# MBot.net
KiCad netlist of a schematic drawn in EAGLE
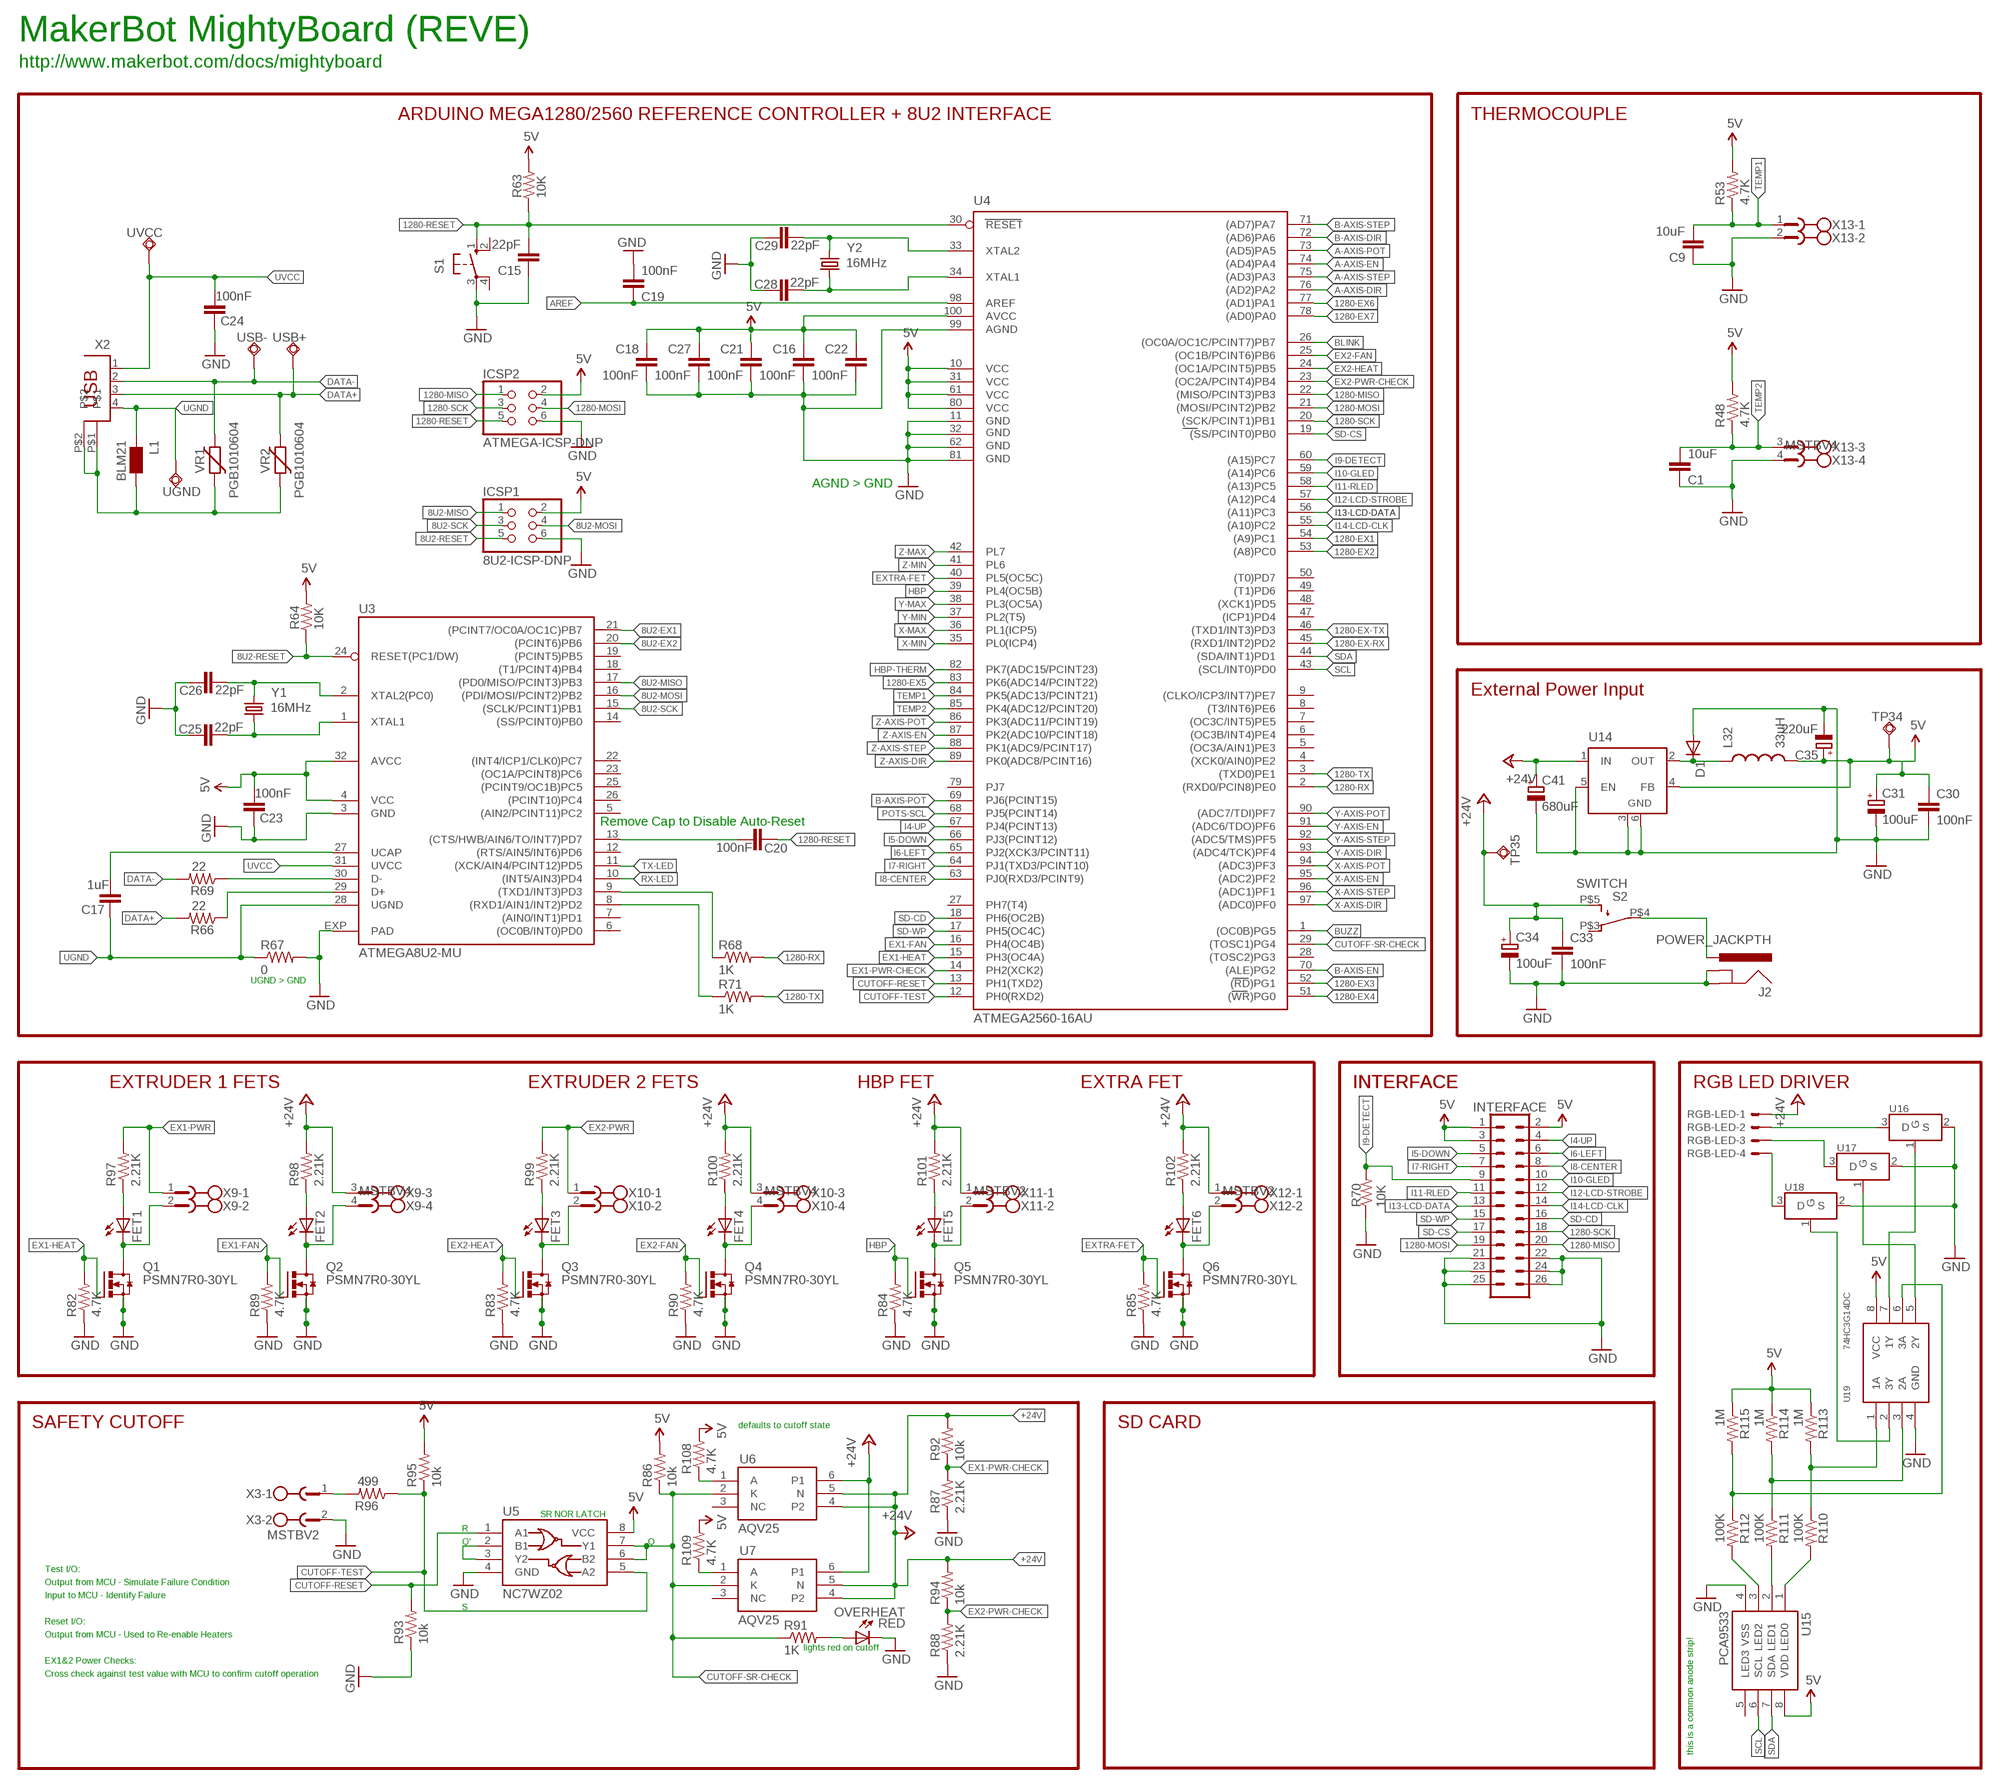
[diagram p0: schematic, sheet 1, part 1 of 2]
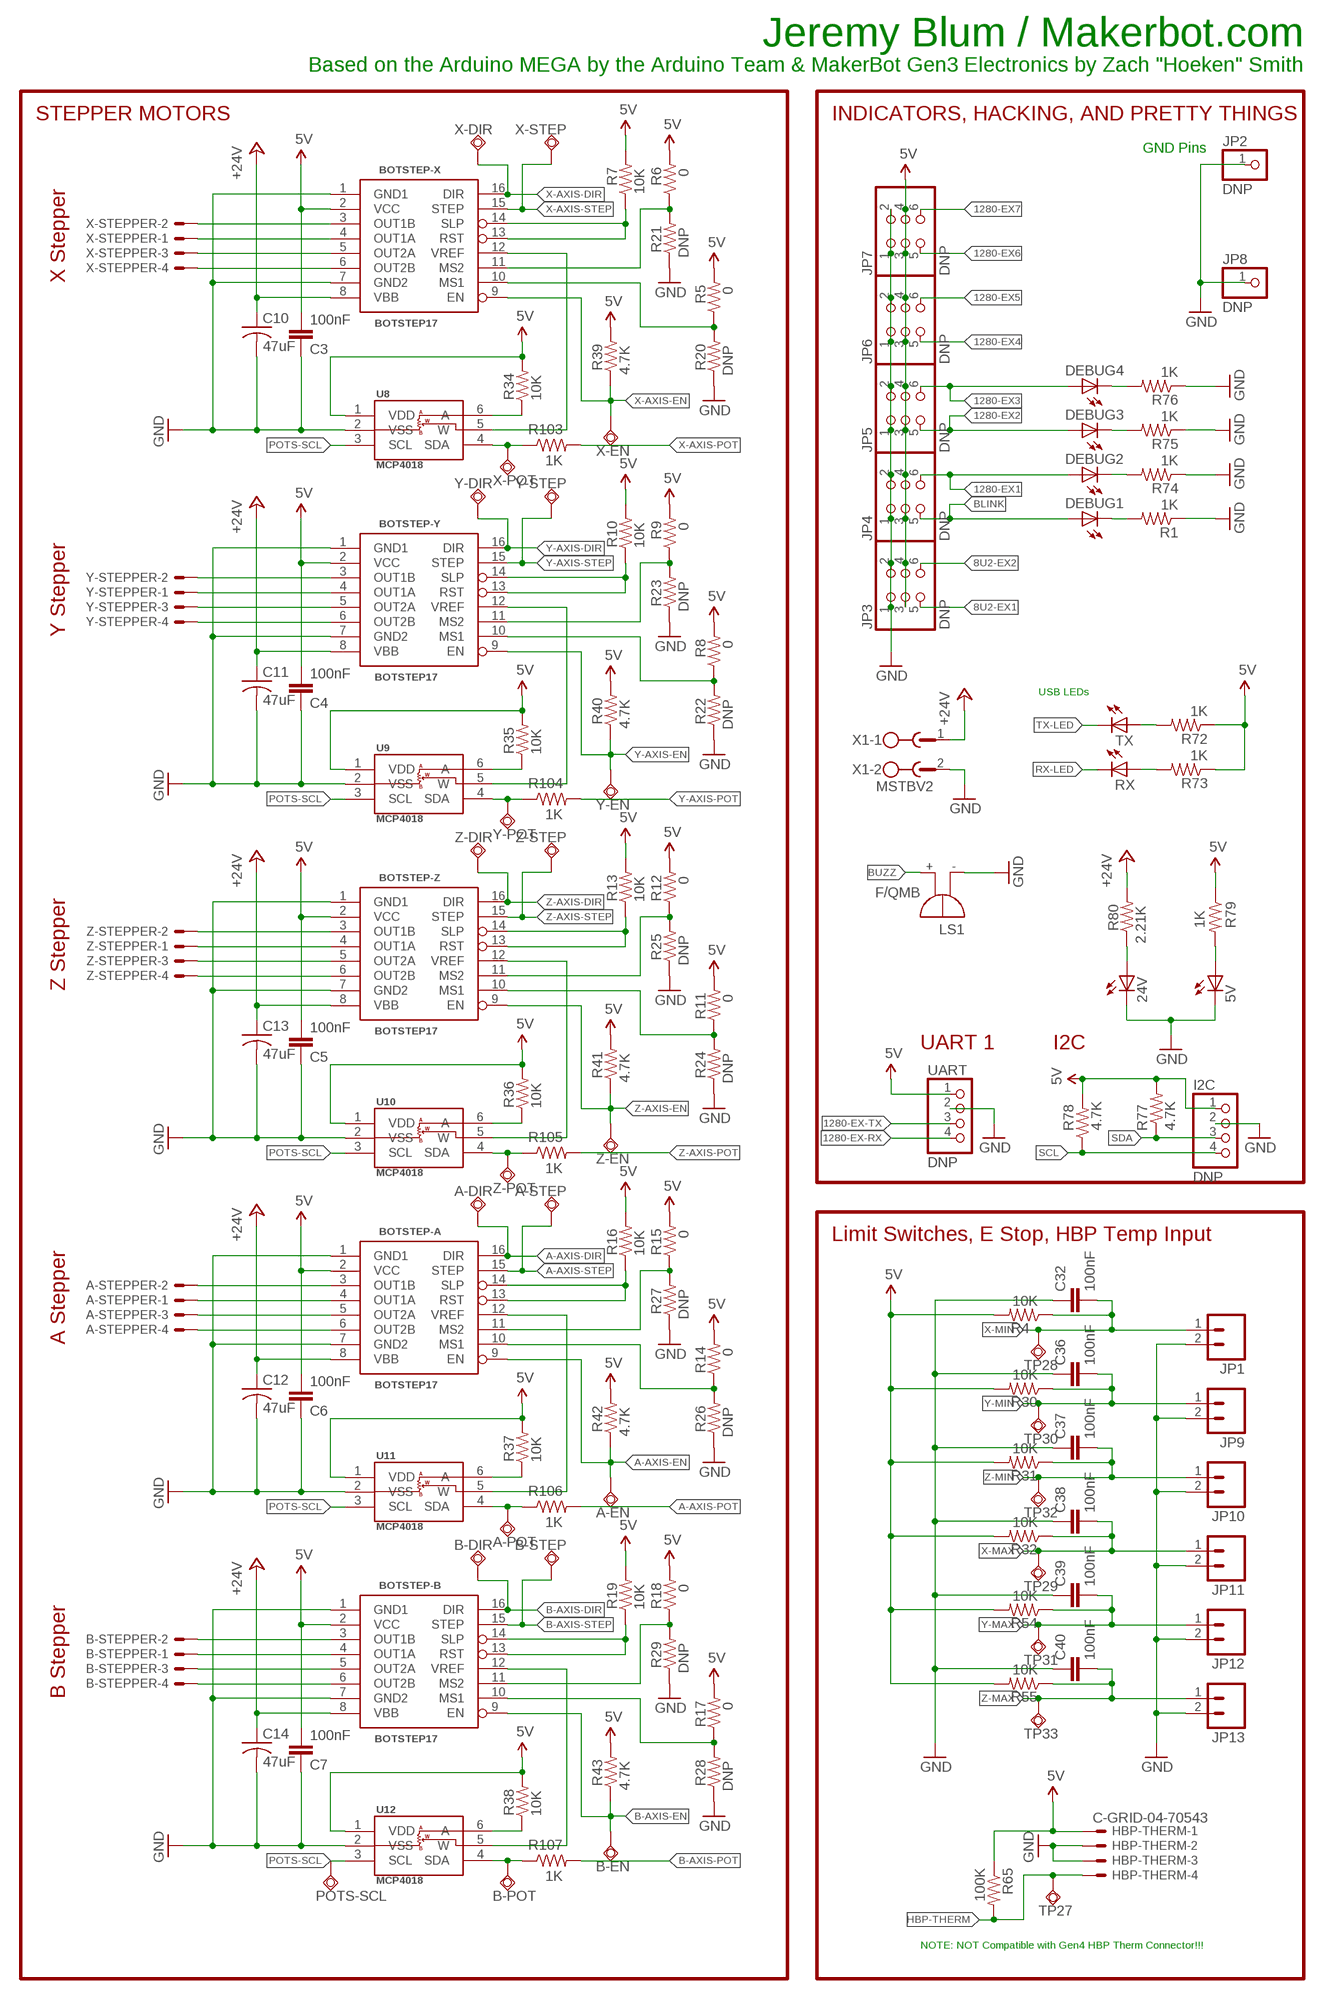
[diagram p1: schematic, sheet 1, part 2 of 2]

(export (version "E")
  (design (tool "Eeschema 10.0.6"))
  (components
    (comp (ref "5V")
      (value "GREEN")
      (footprint "eagle-import:LED-0805")
      (libsource (lib "eagle-import") (part "LED0805"))
    )
    (comp (ref "24V")
      (value "GREEN")
      (footprint "eagle-import:LED-0805")
      (libsource (lib "eagle-import") (part "LED0805"))
    )
    (comp (ref "A-DIR")
      (value "TPSQTP09R")
      (footprint "eagle-import:TP09R")
      (libsource (lib "eagle-import") (part "TPSQTP09R"))
    )
    (comp (ref "A-EN")
      (value "TPSQTP09R")
      (footprint "eagle-import:TP09R")
      (libsource (lib "eagle-import") (part "TPSQTP09R"))
    )
    (comp (ref "A-POT")
      (value "TPSQTP09R")
      (footprint "eagle-import:TP09R")
      (libsource (lib "eagle-import") (part "TPSQTP09R"))
    )
    (comp (ref "A-STEP")
      (value "TPSQTP09R")
      (footprint "eagle-import:TP09R")
      (libsource (lib "eagle-import") (part "TPSQTP09R"))
    )
    (comp (ref "A-STEPPER")
      (value "KK-156-4")
      (footprint "eagle-import:KK-156-4")
      (libsource (lib "eagle-import") (part "KK-156-4"))
    )
    (comp (ref "B-DIR")
      (value "TPSQTP09R")
      (footprint "eagle-import:TP09R")
      (libsource (lib "eagle-import") (part "TPSQTP09R"))
    )
    (comp (ref "B-EN")
      (value "TPSQTP09R")
      (footprint "eagle-import:TP09R")
      (libsource (lib "eagle-import") (part "TPSQTP09R"))
    )
    (comp (ref "B-POT")
      (value "TPSQTP09R")
      (footprint "eagle-import:TP09R")
      (libsource (lib "eagle-import") (part "TPSQTP09R"))
    )
    (comp (ref "B-STEP")
      (value "TPSQTP09R")
      (footprint "eagle-import:TP09R")
      (libsource (lib "eagle-import") (part "TPSQTP09R"))
    )
    (comp (ref "B-STEPPER")
      (value "KK-156-4")
      (footprint "eagle-import:KK-156-4")
      (libsource (lib "eagle-import") (part "KK-156-4"))
    )
    (comp (ref "BOTSTEP-A")
      (value "BOTSTEP17")
      (footprint "eagle-import:BOTSTEP17-INV")
      (libsource (lib "eagle-import") (part "BOTSTEP17CHIP-DOWN"))
    )
    (comp (ref "BOTSTEP-B")
      (value "BOTSTEP17")
      (footprint "eagle-import:BOTSTEP17-INV")
      (libsource (lib "eagle-import") (part "BOTSTEP17CHIP-DOWN"))
    )
    (comp (ref "BOTSTEP-X")
      (value "BOTSTEP17")
      (footprint "eagle-import:BOTSTEP17-INV")
      (libsource (lib "eagle-import") (part "BOTSTEP17CHIP-DOWN"))
    )
    (comp (ref "BOTSTEP-Y")
      (value "BOTSTEP17")
      (footprint "eagle-import:BOTSTEP17-INV")
      (libsource (lib "eagle-import") (part "BOTSTEP17CHIP-DOWN"))
    )
    (comp (ref "BOTSTEP-Z")
      (value "BOTSTEP17")
      (footprint "eagle-import:BOTSTEP17-INV")
      (libsource (lib "eagle-import") (part "BOTSTEP17CHIP-DOWN"))
    )
    (comp (ref "C1")
      (value "10uF")
      (footprint "eagle-import:0805")
      (libsource (lib "eagle-import") (part "CAP0805"))
    )
    (comp (ref "C3")
      (value "100nF")
      (footprint "eagle-import:0805")
      (libsource (lib "eagle-import") (part "CAP0805"))
    )
    (comp (ref "C4")
      (value "100nF")
      (footprint "eagle-import:0805")
      (libsource (lib "eagle-import") (part "CAP0805"))
    )
    (comp (ref "C5")
      (value "100nF")
      (footprint "eagle-import:0805")
      (libsource (lib "eagle-import") (part "CAP0805"))
    )
    (comp (ref "C6")
      (value "100nF")
      (footprint "eagle-import:0805")
      (libsource (lib "eagle-import") (part "CAP0805"))
    )
    (comp (ref "C7")
      (value "100nF")
      (footprint "eagle-import:0805")
      (libsource (lib "eagle-import") (part "CAP0805"))
    )
    (comp (ref "C9")
      (value "10uF")
      (footprint "eagle-import:0805")
      (libsource (lib "eagle-import") (part "CAP0805"))
    )
    (comp (ref "C10")
      (value "47uF")
      (footprint "eagle-import:CAP2917")
      (libsource (lib "eagle-import") (part "C-US"))
    )
    (comp (ref "C11")
      (value "47uF")
      (footprint "eagle-import:CAP2917")
      (libsource (lib "eagle-import") (part "C-US"))
    )
    (comp (ref "C12")
      (value "47uF")
      (footprint "eagle-import:CAP2917")
      (libsource (lib "eagle-import") (part "C-US"))
    )
    (comp (ref "C13")
      (value "47uF")
      (footprint "eagle-import:CAP2917")
      (libsource (lib "eagle-import") (part "C-US"))
    )
    (comp (ref "C14")
      (value "47uF")
      (footprint "eagle-import:CAP2917")
      (libsource (lib "eagle-import") (part "C-US"))
    )
    (comp (ref "C15")
      (value "22pF")
      (footprint "eagle-import:0805")
      (libsource (lib "eagle-import") (part "CAP0805"))
    )
    (comp (ref "C16")
      (value "100nF")
      (footprint "eagle-import:0805")
      (libsource (lib "eagle-import") (part "CAP0805"))
    )
    (comp (ref "C17")
      (value "1uF")
      (footprint "eagle-import:0805")
      (libsource (lib "eagle-import") (part "CAP0805"))
    )
    (comp (ref "C18")
      (value "100nF")
      (footprint "eagle-import:0805")
      (libsource (lib "eagle-import") (part "CAP0805"))
    )
    (comp (ref "C19")
      (value "100nF")
      (footprint "eagle-import:0805")
      (libsource (lib "eagle-import") (part "CAP0805"))
    )
    (comp (ref "C20")
      (value "100nF")
      (footprint "eagle-import:0805")
      (libsource (lib "eagle-import") (part "CAP0805"))
    )
    (comp (ref "C21")
      (value "100nF")
      (footprint "eagle-import:0805")
      (libsource (lib "eagle-import") (part "CAP0805"))
    )
    (comp (ref "C22")
      (value "100nF")
      (footprint "eagle-import:0805")
      (libsource (lib "eagle-import") (part "CAP0805"))
    )
    (comp (ref "C23")
      (value "100nF")
      (footprint "eagle-import:0805")
      (libsource (lib "eagle-import") (part "CAP0805"))
    )
    (comp (ref "C24")
      (value "100nF")
      (footprint "eagle-import:0805")
      (libsource (lib "eagle-import") (part "CAP0805"))
    )
    (comp (ref "C25")
      (value "22pF")
      (footprint "eagle-import:0805")
      (libsource (lib "eagle-import") (part "CAP0805"))
    )
    (comp (ref "C26")
      (value "22pF")
      (footprint "eagle-import:0805")
      (libsource (lib "eagle-import") (part "CAP0805"))
    )
    (comp (ref "C27")
      (value "100nF")
      (footprint "eagle-import:0805")
      (libsource (lib "eagle-import") (part "CAP0805"))
    )
    (comp (ref "C28")
      (value "22pF")
      (footprint "eagle-import:0805")
      (libsource (lib "eagle-import") (part "CAP0805"))
    )
    (comp (ref "C29")
      (value "22pF")
      (footprint "eagle-import:0805")
      (libsource (lib "eagle-import") (part "CAP0805"))
    )
    (comp (ref "C30")
      (value "100nF")
      (footprint "eagle-import:0805")
      (libsource (lib "eagle-import") (part "CAP0805"))
    )
    (comp (ref "C31")
      (value "100uF")
      (footprint "eagle-import:E3,5-8")
      (libsource (lib "eagle-import") (part "CPOL-EUE3.5-8"))
    )
    (comp (ref "C32")
      (value "100nF")
      (footprint "eagle-import:0805")
      (libsource (lib "eagle-import") (part "CAP0805"))
    )
    (comp (ref "C33")
      (value "100nF")
      (footprint "eagle-import:0805")
      (libsource (lib "eagle-import") (part "CAP0805"))
    )
    (comp (ref "C34")
      (value "100uF")
      (footprint "eagle-import:E3,5-8")
      (libsource (lib "eagle-import") (part "CPOL-EUE3.5-8"))
    )
    (comp (ref "C35")
      (value "220uF")
      (footprint "eagle-import:E3,5-8")
      (libsource (lib "eagle-import") (part "CPOL-EUE3.5-8"))
    )
    (comp (ref "C36")
      (value "100nF")
      (footprint "eagle-import:0805")
      (libsource (lib "eagle-import") (part "CAP0805"))
    )
    (comp (ref "C37")
      (value "100nF")
      (footprint "eagle-import:0805")
      (libsource (lib "eagle-import") (part "CAP0805"))
    )
    (comp (ref "C38")
      (value "100nF")
      (footprint "eagle-import:0805")
      (libsource (lib "eagle-import") (part "CAP0805"))
    )
    (comp (ref "C39")
      (value "100nF")
      (footprint "eagle-import:0805")
      (libsource (lib "eagle-import") (part "CAP0805"))
    )
    (comp (ref "C40")
      (value "100nF")
      (footprint "eagle-import:0805")
      (libsource (lib "eagle-import") (part "CAP0805"))
    )
    (comp (ref "C41")
      (value "680uF")
      (footprint "eagle-import:E3,5-8")
      (libsource (lib "eagle-import") (part "CPOL-EUE3.5-8"))
    )
    (comp (ref "D1")
      (value "DIODESMB")
      (footprint "eagle-import:SMB-DIODE")
      (libsource (lib "eagle-import") (part "DIODESMB"))
    )
    (comp (ref "DEBUG1")
      (value "GREEN")
      (footprint "eagle-import:LED-0805")
      (libsource (lib "eagle-import") (part "LED0805"))
    )
    (comp (ref "DEBUG2")
      (value "GREEN")
      (footprint "eagle-import:LED-0805")
      (libsource (lib "eagle-import") (part "LED0805"))
    )
    (comp (ref "DEBUG3")
      (value "GREEN")
      (footprint "eagle-import:LED-0805")
      (libsource (lib "eagle-import") (part "LED0805"))
    )
    (comp (ref "DEBUG4")
      (value "GREEN")
      (footprint "eagle-import:LED-0805")
      (libsource (lib "eagle-import") (part "LED0805"))
    )
    (comp (ref "FET1")
      (value "GREEN")
      (footprint "eagle-import:LED-0805")
      (libsource (lib "eagle-import") (part "LED0805"))
    )
    (comp (ref "FET2")
      (value "GREEN")
      (footprint "eagle-import:LED-0805")
      (libsource (lib "eagle-import") (part "LED0805"))
    )
    (comp (ref "FET3")
      (value "GREEN")
      (footprint "eagle-import:LED-0805")
      (libsource (lib "eagle-import") (part "LED0805"))
    )
    (comp (ref "FET4")
      (value "GREEN")
      (footprint "eagle-import:LED-0805")
      (libsource (lib "eagle-import") (part "LED0805"))
    )
    (comp (ref "FET5")
      (value "GREEN")
      (footprint "eagle-import:LED-0805")
      (libsource (lib "eagle-import") (part "LED0805"))
    )
    (comp (ref "FET6")
      (value "GREEN")
      (footprint "eagle-import:LED-0805")
      (libsource (lib "eagle-import") (part "LED0805"))
    )
    (comp (ref "HBP-THERM")
      (value "C-GRID-04-70543")
      (footprint "eagle-import:70543-04")
      (libsource (lib "eagle-import") (part "C-GRID-04-70543"))
    )
    (comp (ref "I2C")
      (value "DNP")
      (footprint "eagle-import:1X04")
      (libsource (lib "eagle-import") (part "PINHD-1X4"))
    )
    (comp (ref "ICSP1")
      (value "8U2-ICSP-DNP")
      (footprint "eagle-import:2X03")
      (libsource (lib "eagle-import") (part "PINHD-2X3"))
    )
    (comp (ref "ICSP2")
      (value "ATMEGA-ICSP-DNP")
      (footprint "eagle-import:2X03")
      (libsource (lib "eagle-import") (part "PINHD-2X3"))
    )
    (comp (ref "INTERFACE")
      (value "ML26")
      (footprint "eagle-import:ML26")
      (libsource (lib "eagle-import") (part "ML26"))
    )
    (comp (ref "J2")
      (value "POWER_JACKPTH")
      (footprint "eagle-import:POWER_JACK_PTH")
      (libsource (lib "eagle-import") (part "POWER_JACKPTH"))
    )
    (comp (ref "JP1")
      (value "M02POLAR")
      (footprint "eagle-import:MOLEX-1X2")
      (libsource (lib "eagle-import") (part "M02POLAR"))
    )
    (comp (ref "JP2")
      (value "DNP")
      (footprint "eagle-import:1X01")
      (libsource (lib "eagle-import") (part "PINHD-1X1"))
    )
    (comp (ref "JP3")
      (value "DNP")
      (footprint "eagle-import:2X03")
      (libsource (lib "eagle-import") (part "PINHD-2X3"))
    )
    (comp (ref "JP4")
      (value "DNP")
      (footprint "eagle-import:2X03")
      (libsource (lib "eagle-import") (part "PINHD-2X3"))
    )
    (comp (ref "JP5")
      (value "DNP")
      (footprint "eagle-import:2X03")
      (libsource (lib "eagle-import") (part "PINHD-2X3"))
    )
    (comp (ref "JP6")
      (value "DNP")
      (footprint "eagle-import:2X03")
      (libsource (lib "eagle-import") (part "PINHD-2X3"))
    )
    (comp (ref "JP7")
      (value "DNP")
      (footprint "eagle-import:2X03")
      (libsource (lib "eagle-import") (part "PINHD-2X3"))
    )
    (comp (ref "JP8")
      (value "DNP")
      (footprint "eagle-import:1X01")
      (libsource (lib "eagle-import") (part "PINHD-1X1"))
    )
    (comp (ref "JP9")
      (value "M02POLAR")
      (footprint "eagle-import:MOLEX-1X2")
      (libsource (lib "eagle-import") (part "M02POLAR"))
    )
    (comp (ref "JP10")
      (value "M02POLAR")
      (footprint "eagle-import:MOLEX-1X2")
      (libsource (lib "eagle-import") (part "M02POLAR"))
    )
    (comp (ref "JP11")
      (value "M02POLAR")
      (footprint "eagle-import:MOLEX-1X2")
      (libsource (lib "eagle-import") (part "M02POLAR"))
    )
    (comp (ref "JP12")
      (value "M02POLAR")
      (footprint "eagle-import:MOLEX-1X2")
      (libsource (lib "eagle-import") (part "M02POLAR"))
    )
    (comp (ref "JP13")
      (value "M02POLAR")
      (footprint "eagle-import:MOLEX-1X2")
      (libsource (lib "eagle-import") (part "M02POLAR"))
    )
    (comp (ref "L1")
      (value "BLM21")
      (footprint "eagle-import:0805")
      (libsource (lib "eagle-import") (part "WE-CBF_0805"))
    )
    (comp (ref "L32")
      (value "33uH")
      (footprint "eagle-import:CDRH125")
      (libsource (lib "eagle-import") (part "INDUCTORPWR"))
    )
    (comp (ref "LS1")
      (value "F/QMB")
      (footprint "eagle-import:F_QMB")
      (libsource (lib "eagle-import") (part "F/QMB"))
    )
    (comp (ref "OVERHEAT")
      (value "RED")
      (footprint "eagle-import:LED-0805")
      (libsource (lib "eagle-import") (part "LED0805"))
    )
    (comp (ref "POTS-SCL")
      (value "TPSQTP09R")
      (footprint "eagle-import:TP09R")
      (libsource (lib "eagle-import") (part "TPSQTP09R"))
    )
    (comp (ref "Q1")
      (value "PSMN7R0-30YL")
      (footprint "eagle-import:SOT669")
      (libsource (lib "eagle-import") (part "PSMN7R0-30YL"))
    )
    (comp (ref "Q2")
      (value "PSMN7R0-30YL")
      (footprint "eagle-import:SOT669")
      (libsource (lib "eagle-import") (part "PSMN7R0-30YL"))
    )
    (comp (ref "Q3")
      (value "PSMN7R0-30YL")
      (footprint "eagle-import:SOT669")
      (libsource (lib "eagle-import") (part "PSMN7R0-30YL"))
    )
    (comp (ref "Q4")
      (value "PSMN7R0-30YL")
      (footprint "eagle-import:SOT669")
      (libsource (lib "eagle-import") (part "PSMN7R0-30YL"))
    )
    (comp (ref "Q5")
      (value "PSMN7R0-30YL")
      (footprint "eagle-import:SOT669")
      (libsource (lib "eagle-import") (part "PSMN7R0-30YL"))
    )
    (comp (ref "Q6")
      (value "PSMN7R0-30YL")
      (footprint "eagle-import:SOT669")
      (libsource (lib "eagle-import") (part "PSMN7R0-30YL"))
    )
    (comp (ref "R1")
      (value "1K")
      (footprint "eagle-import:0805")
      (libsource (lib "eagle-import") (part "RESISTOR"))
    )
    (comp (ref "R4")
      (value "10K")
      (footprint "eagle-import:0805")
      (libsource (lib "eagle-import") (part "RESISTOR"))
    )
    (comp (ref "R5")
      (value "0")
      (footprint "eagle-import:0805")
      (libsource (lib "eagle-import") (part "RESISTOR"))
    )
    (comp (ref "R6")
      (value "0")
      (footprint "eagle-import:0805")
      (libsource (lib "eagle-import") (part "RESISTOR"))
    )
    (comp (ref "R7")
      (value "10K")
      (footprint "eagle-import:0805")
      (libsource (lib "eagle-import") (part "RESISTOR"))
    )
    (comp (ref "R8")
      (value "0")
      (footprint "eagle-import:0805")
      (libsource (lib "eagle-import") (part "RESISTOR"))
    )
    (comp (ref "R9")
      (value "0")
      (footprint "eagle-import:0805")
      (libsource (lib "eagle-import") (part "RESISTOR"))
    )
    (comp (ref "R10")
      (value "10K")
      (footprint "eagle-import:0805")
      (libsource (lib "eagle-import") (part "RESISTOR"))
    )
    (comp (ref "R11")
      (value "0")
      (footprint "eagle-import:0805")
      (libsource (lib "eagle-import") (part "RESISTOR"))
    )
    (comp (ref "R12")
      (value "0")
      (footprint "eagle-import:0805")
      (libsource (lib "eagle-import") (part "RESISTOR"))
    )
    (comp (ref "R13")
      (value "10K")
      (footprint "eagle-import:0805")
      (libsource (lib "eagle-import") (part "RESISTOR"))
    )
    (comp (ref "R14")
      (value "0")
      (footprint "eagle-import:0805")
      (libsource (lib "eagle-import") (part "RESISTOR"))
    )
    (comp (ref "R15")
      (value "0")
      (footprint "eagle-import:0805")
      (libsource (lib "eagle-import") (part "RESISTOR"))
    )
    (comp (ref "R16")
      (value "10K")
      (footprint "eagle-import:0805")
      (libsource (lib "eagle-import") (part "RESISTOR"))
    )
    (comp (ref "R17")
      (value "0")
      (footprint "eagle-import:0805")
      (libsource (lib "eagle-import") (part "RESISTOR"))
    )
    (comp (ref "R18")
      (value "0")
      (footprint "eagle-import:0805")
      (libsource (lib "eagle-import") (part "RESISTOR"))
    )
    (comp (ref "R19")
      (value "10K")
      (footprint "eagle-import:0805")
      (libsource (lib "eagle-import") (part "RESISTOR"))
    )
    (comp (ref "R20")
      (value "DNP")
      (footprint "eagle-import:0805")
      (libsource (lib "eagle-import") (part "RESISTOR"))
    )
    (comp (ref "R21")
      (value "DNP")
      (footprint "eagle-import:0805")
      (libsource (lib "eagle-import") (part "RESISTOR"))
    )
    (comp (ref "R22")
      (value "DNP")
      (footprint "eagle-import:0805")
      (libsource (lib "eagle-import") (part "RESISTOR"))
    )
    (comp (ref "R23")
      (value "DNP")
      (footprint "eagle-import:0805")
      (libsource (lib "eagle-import") (part "RESISTOR"))
    )
    (comp (ref "R24")
      (value "DNP")
      (footprint "eagle-import:0805")
      (libsource (lib "eagle-import") (part "RESISTOR"))
    )
    (comp (ref "R25")
      (value "DNP")
      (footprint "eagle-import:0805")
      (libsource (lib "eagle-import") (part "RESISTOR"))
    )
    (comp (ref "R26")
      (value "DNP")
      (footprint "eagle-import:0805")
      (libsource (lib "eagle-import") (part "RESISTOR"))
    )
    (comp (ref "R27")
      (value "DNP")
      (footprint "eagle-import:0805")
      (libsource (lib "eagle-import") (part "RESISTOR"))
    )
    (comp (ref "R28")
      (value "DNP")
      (footprint "eagle-import:0805")
      (libsource (lib "eagle-import") (part "RESISTOR"))
    )
    (comp (ref "R29")
      (value "DNP")
      (footprint "eagle-import:0805")
      (libsource (lib "eagle-import") (part "RESISTOR"))
    )
    (comp (ref "R30")
      (value "10K")
      (footprint "eagle-import:0805")
      (libsource (lib "eagle-import") (part "RESISTOR"))
    )
    (comp (ref "R31")
      (value "10K")
      (footprint "eagle-import:0805")
      (libsource (lib "eagle-import") (part "RESISTOR"))
    )
    (comp (ref "R32")
      (value "10K")
      (footprint "eagle-import:0805")
      (libsource (lib "eagle-import") (part "RESISTOR"))
    )
    (comp (ref "R34")
      (value "10K")
      (footprint "eagle-import:0805")
      (libsource (lib "eagle-import") (part "RESISTOR"))
    )
    (comp (ref "R35")
      (value "10K")
      (footprint "eagle-import:0805")
      (libsource (lib "eagle-import") (part "RESISTOR"))
    )
    (comp (ref "R36")
      (value "10K")
      (footprint "eagle-import:0805")
      (libsource (lib "eagle-import") (part "RESISTOR"))
    )
    (comp (ref "R37")
      (value "10K")
      (footprint "eagle-import:0805")
      (libsource (lib "eagle-import") (part "RESISTOR"))
    )
    (comp (ref "R38")
      (value "10K")
      (footprint "eagle-import:0805")
      (libsource (lib "eagle-import") (part "RESISTOR"))
    )
    (comp (ref "R39")
      (value "4.7K")
      (footprint "eagle-import:0805")
      (libsource (lib "eagle-import") (part "RESISTOR"))
    )
    (comp (ref "R40")
      (value "4.7K")
      (footprint "eagle-import:0805")
      (libsource (lib "eagle-import") (part "RESISTOR"))
    )
    (comp (ref "R41")
      (value "4.7K")
      (footprint "eagle-import:0805")
      (libsource (lib "eagle-import") (part "RESISTOR"))
    )
    (comp (ref "R42")
      (value "4.7K")
      (footprint "eagle-import:0805")
      (libsource (lib "eagle-import") (part "RESISTOR"))
    )
    (comp (ref "R43")
      (value "4.7K")
      (footprint "eagle-import:0805")
      (libsource (lib "eagle-import") (part "RESISTOR"))
    )
    (comp (ref "R48")
      (value "4.7K")
      (footprint "eagle-import:0805")
      (libsource (lib "eagle-import") (part "RESISTOR"))
    )
    (comp (ref "R53")
      (value "4.7K")
      (footprint "eagle-import:0805")
      (libsource (lib "eagle-import") (part "RESISTOR"))
    )
    (comp (ref "R54")
      (value "10K")
      (footprint "eagle-import:0805")
      (libsource (lib "eagle-import") (part "RESISTOR"))
    )
    (comp (ref "R55")
      (value "10K")
      (footprint "eagle-import:0805")
      (libsource (lib "eagle-import") (part "RESISTOR"))
    )
    (comp (ref "R63")
      (value "10K")
      (footprint "eagle-import:0805")
      (libsource (lib "eagle-import") (part "RESISTOR"))
    )
    (comp (ref "R64")
      (value "10K")
      (footprint "eagle-import:0805")
      (libsource (lib "eagle-import") (part "RESISTOR"))
    )
    (comp (ref "R65")
      (value "100K")
      (footprint "eagle-import:0805")
      (libsource (lib "eagle-import") (part "RESISTOR"))
    )
    (comp (ref "R66")
      (value "22")
      (footprint "eagle-import:0805")
      (libsource (lib "eagle-import") (part "RESISTOR"))
    )
    (comp (ref "R67")
      (value "0")
      (footprint "eagle-import:0805")
      (libsource (lib "eagle-import") (part "RESISTOR"))
    )
    (comp (ref "R68")
      (value "1K")
      (footprint "eagle-import:0805")
      (libsource (lib "eagle-import") (part "RESISTOR"))
    )
    (comp (ref "R69")
      (value "22")
      (footprint "eagle-import:0805")
      (libsource (lib "eagle-import") (part "RESISTOR"))
    )
    (comp (ref "R70")
      (value "10K")
      (footprint "eagle-import:0805")
      (libsource (lib "eagle-import") (part "RESISTOR"))
    )
    (comp (ref "R71")
      (value "1K")
      (footprint "eagle-import:0805")
      (libsource (lib "eagle-import") (part "RESISTOR"))
    )
    (comp (ref "R72")
      (value "1K")
      (footprint "eagle-import:0805")
      (libsource (lib "eagle-import") (part "RESISTOR"))
    )
    (comp (ref "R73")
      (value "1K")
      (footprint "eagle-import:0805")
      (libsource (lib "eagle-import") (part "RESISTOR"))
    )
    (comp (ref "R74")
      (value "1K")
      (footprint "eagle-import:0805")
      (libsource (lib "eagle-import") (part "RESISTOR"))
    )
    (comp (ref "R75")
      (value "1K")
      (footprint "eagle-import:0805")
      (libsource (lib "eagle-import") (part "RESISTOR"))
    )
    (comp (ref "R76")
      (value "1K")
      (footprint "eagle-import:0805")
      (libsource (lib "eagle-import") (part "RESISTOR"))
    )
    (comp (ref "R77")
      (value "4.7K")
      (footprint "eagle-import:0805")
      (libsource (lib "eagle-import") (part "RESISTOR"))
    )
    (comp (ref "R78")
      (value "4.7K")
      (footprint "eagle-import:0805")
      (libsource (lib "eagle-import") (part "RESISTOR"))
    )
    (comp (ref "R79")
      (value "1K")
      (footprint "eagle-import:0805")
      (libsource (lib "eagle-import") (part "RESISTOR"))
    )
    (comp (ref "R80")
      (value "2.21K")
      (footprint "eagle-import:0805")
      (libsource (lib "eagle-import") (part "RESISTOR"))
    )
    (comp (ref "R82")
      (value "4.7K")
      (footprint "eagle-import:0805")
      (libsource (lib "eagle-import") (part "RESISTOR"))
    )
    (comp (ref "R83")
      (value "4.7K")
      (footprint "eagle-import:0805")
      (libsource (lib "eagle-import") (part "RESISTOR"))
    )
    (comp (ref "R84")
      (value "4.7K")
      (footprint "eagle-import:0805")
      (libsource (lib "eagle-import") (part "RESISTOR"))
    )
    (comp (ref "R85")
      (value "4.7K")
      (footprint "eagle-import:0805")
      (libsource (lib "eagle-import") (part "RESISTOR"))
    )
    (comp (ref "R86")
      (value "10k")
      (footprint "eagle-import:0805")
      (libsource (lib "eagle-import") (part "RESISTOR"))
    )
    (comp (ref "R87")
      (value "2.21K")
      (footprint "eagle-import:0805")
      (libsource (lib "eagle-import") (part "RESISTOR"))
    )
    (comp (ref "R88")
      (value "2.21K")
      (footprint "eagle-import:0805")
      (libsource (lib "eagle-import") (part "RESISTOR"))
    )
    (comp (ref "R89")
      (value "4.7K")
      (footprint "eagle-import:0805")
      (libsource (lib "eagle-import") (part "RESISTOR"))
    )
    (comp (ref "R90")
      (value "4.7K")
      (footprint "eagle-import:0805")
      (libsource (lib "eagle-import") (part "RESISTOR"))
    )
    (comp (ref "R91")
      (value "1K")
      (footprint "eagle-import:0805")
      (libsource (lib "eagle-import") (part "RESISTOR"))
    )
    (comp (ref "R92")
      (value "10k")
      (footprint "eagle-import:0805")
      (libsource (lib "eagle-import") (part "RESISTOR"))
    )
    (comp (ref "R93")
      (value "10k")
      (footprint "eagle-import:0805")
      (libsource (lib "eagle-import") (part "RESISTOR"))
    )
    (comp (ref "R94")
      (value "10k")
      (footprint "eagle-import:0805")
      (libsource (lib "eagle-import") (part "RESISTOR"))
    )
    (comp (ref "R95")
      (value "10k")
      (footprint "eagle-import:0805")
      (libsource (lib "eagle-import") (part "RESISTOR"))
    )
    (comp (ref "R96")
      (value "499")
      (footprint "eagle-import:0805")
      (libsource (lib "eagle-import") (part "RESISTOR"))
    )
    (comp (ref "R97")
      (value "2.21K")
      (footprint "eagle-import:0805")
      (libsource (lib "eagle-import") (part "RESISTOR"))
    )
    (comp (ref "R98")
      (value "2.21K")
      (footprint "eagle-import:0805")
      (libsource (lib "eagle-import") (part "RESISTOR"))
    )
    (comp (ref "R99")
      (value "2.21K")
      (footprint "eagle-import:0805")
      (libsource (lib "eagle-import") (part "RESISTOR"))
    )
    (comp (ref "R100")
      (value "2.21K")
      (footprint "eagle-import:0805")
      (libsource (lib "eagle-import") (part "RESISTOR"))
    )
    (comp (ref "R101")
      (value "2.21K")
      (footprint "eagle-import:0805")
      (libsource (lib "eagle-import") (part "RESISTOR"))
    )
    (comp (ref "R102")
      (value "2.21K")
      (footprint "eagle-import:0805")
      (libsource (lib "eagle-import") (part "RESISTOR"))
    )
    (comp (ref "R103")
      (value "1K")
      (footprint "eagle-import:0805")
      (libsource (lib "eagle-import") (part "RESISTOR"))
    )
    (comp (ref "R104")
      (value "1K")
      (footprint "eagle-import:0805")
      (libsource (lib "eagle-import") (part "RESISTOR"))
    )
    (comp (ref "R105")
      (value "1K")
      (footprint "eagle-import:0805")
      (libsource (lib "eagle-import") (part "RESISTOR"))
    )
    (comp (ref "R106")
      (value "1K")
      (footprint "eagle-import:0805")
      (libsource (lib "eagle-import") (part "RESISTOR"))
    )
    (comp (ref "R107")
      (value "1K")
      (footprint "eagle-import:0805")
      (libsource (lib "eagle-import") (part "RESISTOR"))
    )
    (comp (ref "R108")
      (value "4.7K")
      (footprint "eagle-import:0805")
      (libsource (lib "eagle-import") (part "RESISTOR"))
    )
    (comp (ref "R109")
      (value "4.7K")
      (footprint "eagle-import:0805")
      (libsource (lib "eagle-import") (part "RESISTOR"))
    )
    (comp (ref "R110")
      (value "100K")
      (footprint "eagle-import:0805")
      (libsource (lib "eagle-import") (part "RESISTOR"))
    )
    (comp (ref "R111")
      (value "100K")
      (footprint "eagle-import:0805")
      (libsource (lib "eagle-import") (part "RESISTOR"))
    )
    (comp (ref "R112")
      (value "100K")
      (footprint "eagle-import:0805")
      (libsource (lib "eagle-import") (part "RESISTOR"))
    )
    (comp (ref "R113")
      (value "1M")
      (footprint "eagle-import:0805")
      (libsource (lib "eagle-import") (part "RESISTOR"))
    )
    (comp (ref "R114")
      (value "1M")
      (footprint "eagle-import:0805")
      (libsource (lib "eagle-import") (part "RESISTOR"))
    )
    (comp (ref "R115")
      (value "1M")
      (footprint "eagle-import:0805")
      (libsource (lib "eagle-import") (part "RESISTOR"))
    )
    (comp (ref "RGB-LED")
      (value "C-GRID-04-70543")
      (footprint "eagle-import:70543-04")
      (libsource (lib "eagle-import") (part "C-GRID-04-70543"))
    )
    (comp (ref "RX")
      (value "GREEN")
      (footprint "eagle-import:LED-0805")
      (libsource (lib "eagle-import") (part "LED0805"))
    )
    (comp (ref "S1")
      (value "10-XX")
      (footprint "eagle-import:B3F-10XX")
      (fields (field (name "MPN") "B3F-1000"))
      (libsource (lib "eagle-import") (part "10-XX"))
    )
    (comp (ref "S2")
      (value "SWITCH")
      (footprint "eagle-import:SWITCH")
      (libsource (lib "eagle-import") (part "SWITCH"))
    )
    (comp (ref "TP27")
      (value "TPSQTP09R")
      (footprint "eagle-import:TP09R")
      (libsource (lib "eagle-import") (part "TPSQTP09R"))
    )
    (comp (ref "TP28")
      (value "TPSQTP09R")
      (footprint "eagle-import:TP09R")
      (libsource (lib "eagle-import") (part "TPSQTP09R"))
    )
    (comp (ref "TP29")
      (value "TPSQTP09R")
      (footprint "eagle-import:TP09R")
      (libsource (lib "eagle-import") (part "TPSQTP09R"))
    )
    (comp (ref "TP30")
      (value "TPSQTP09R")
      (footprint "eagle-import:TP09R")
      (libsource (lib "eagle-import") (part "TPSQTP09R"))
    )
    (comp (ref "TP31")
      (value "TPSQTP09R")
      (footprint "eagle-import:TP09R")
      (libsource (lib "eagle-import") (part "TPSQTP09R"))
    )
    (comp (ref "TP32")
      (value "TPSQTP09R")
      (footprint "eagle-import:TP09R")
      (libsource (lib "eagle-import") (part "TPSQTP09R"))
    )
    (comp (ref "TP33")
      (value "TPSQTP09R")
      (footprint "eagle-import:TP09R")
      (libsource (lib "eagle-import") (part "TPSQTP09R"))
    )
    (comp (ref "TP34")
      (value "TPSQTP09R")
      (footprint "eagle-import:TP09R")
      (libsource (lib "eagle-import") (part "TPSQTP09R"))
    )
    (comp (ref "TP35")
      (value "TPSQTP09R")
      (footprint "eagle-import:TP09R")
      (libsource (lib "eagle-import") (part "TPSQTP09R"))
    )
    (comp (ref "TX")
      (value "GREEN")
      (footprint "eagle-import:LED-0805")
      (libsource (lib "eagle-import") (part "LED0805"))
    )
    (comp (ref "U3")
      (value "ATMEGA8U2-MU")
      (footprint "eagle-import:QFN32")
      (libsource (lib "eagle-import") (part "ATMEGA8U2-MU"))
    )
    (comp (ref "U4")
      (value "ATMEGA2560-16AU")
      (footprint "eagle-import:TQFP100")
      (libsource (lib "eagle-import") (part "ATMEGAAU1280-16"))
    )
    (comp (ref "U5")
      (value "NC7WZ02")
      (footprint "eagle-import:US8")
      (libsource (lib "eagle-import") (part "NC7WZ02"))
    )
    (comp (ref "U6")
      (value "AQV25")
      (footprint "eagle-import:AQV25-DIPSM")
      (libsource (lib "eagle-import") (part "AQV25EXISTS"))
    )
    (comp (ref "U7")
      (value "AQV25")
      (footprint "eagle-import:AQV25-DIPSM")
      (libsource (lib "eagle-import") (part "AQV25EXISTS"))
    )
    (comp (ref "U8")
      (value "MCP4018")
      (footprint "eagle-import:SC70-6L")
      (libsource (lib "eagle-import") (part "MCP4018"))
    )
    (comp (ref "U9")
      (value "MCP4018")
      (footprint "eagle-import:SC70-6L")
      (libsource (lib "eagle-import") (part "MCP4018"))
    )
    (comp (ref "U10")
      (value "MCP4018")
      (footprint "eagle-import:SC70-6L")
      (libsource (lib "eagle-import") (part "MCP4018"))
    )
    (comp (ref "U11")
      (value "MCP4018")
      (footprint "eagle-import:SC70-6L")
      (libsource (lib "eagle-import") (part "MCP4018"))
    )
    (comp (ref "U12")
      (value "MCP4018")
      (footprint "eagle-import:SC70-6L")
      (libsource (lib "eagle-import") (part "MCP4018"))
    )
    (comp (ref "U14")
      (value "LM2596S")
      (footprint "eagle-import:TO263-5")
      (libsource (lib "eagle-import") (part "LM2596S"))
    )
    (comp (ref "U15")
      (value "PCA9533")
      (footprint "eagle-import:SO8")
      (libsource (lib "eagle-import") (part "PCA9533"))
    )
    (comp (ref "U16")
      (value "FDV301N")
      (footprint "eagle-import:SOT-23")
      (libsource (lib "eagle-import") (part "FDV301N"))
    )
    (comp (ref "U17")
      (value "FDV301N")
      (footprint "eagle-import:SOT-23")
      (libsource (lib "eagle-import") (part "FDV301N"))
    )
    (comp (ref "U18")
      (value "FDV301N")
      (footprint "eagle-import:SOT-23")
      (libsource (lib "eagle-import") (part "FDV301N"))
    )
    (comp (ref "U19")
      (value "74HC3G14DC")
      (footprint "eagle-import:VSSOP8")
      (libsource (lib "eagle-import") (part "74HC3G14DC"))
    )
    (comp (ref "UART")
      (value "DNP")
      (footprint "eagle-import:1X04")
      (libsource (lib "eagle-import") (part "PINHD-1X4"))
    )
    (comp (ref "UGND")
      (value "TPSQTP09R")
      (footprint "eagle-import:TP09R")
      (libsource (lib "eagle-import") (part "TPSQTP09R"))
    )
    (comp (ref "USB+")
      (value "TPSQTP09R")
      (footprint "eagle-import:TP09R")
      (libsource (lib "eagle-import") (part "TPSQTP09R"))
    )
    (comp (ref "USB-")
      (value "TPSQTP09R")
      (footprint "eagle-import:TP09R")
      (libsource (lib "eagle-import") (part "TPSQTP09R"))
    )
    (comp (ref "UVCC")
      (value "TPSQTP09R")
      (footprint "eagle-import:TP09R")
      (libsource (lib "eagle-import") (part "TPSQTP09R"))
    )
    (comp (ref "VR1")
      (value "PGB1010604")
      (footprint "eagle-import:CT_CN0603")
      (libsource (lib "eagle-import") (part "VARISTORCN0603"))
    )
    (comp (ref "VR2")
      (value "PGB1010604")
      (footprint "eagle-import:CT_CN0603")
      (libsource (lib "eagle-import") (part "VARISTORCN0603"))
    )
    (comp (ref "X-DIR")
      (value "TPSQTP09R")
      (footprint "eagle-import:TP09R")
      (libsource (lib "eagle-import") (part "TPSQTP09R"))
    )
    (comp (ref "X-EN")
      (value "TPSQTP09R")
      (footprint "eagle-import:TP09R")
      (libsource (lib "eagle-import") (part "TPSQTP09R"))
    )
    (comp (ref "X-POT")
      (value "TPSQTP09R")
      (footprint "eagle-import:TP09R")
      (libsource (lib "eagle-import") (part "TPSQTP09R"))
    )
    (comp (ref "X-STEP")
      (value "TPSQTP09R")
      (footprint "eagle-import:TP09R")
      (libsource (lib "eagle-import") (part "TPSQTP09R"))
    )
    (comp (ref "X-STEPPER")
      (value "KK-156-4")
      (footprint "eagle-import:KK-156-4")
      (libsource (lib "eagle-import") (part "KK-156-4"))
    )
    (comp (ref "X1")
      (value "MSTBV2")
      (footprint "eagle-import:MSTBV2")
      (fields (field (name "MPN") "MSTBV 2,5/2-GF-5.08"))
      (libsource (lib "eagle-import") (part "MSTBV2"))
    )
    (comp (ref "X2")
      (value "USBA")
      (footprint "eagle-import:SMARTPRJ_PN61729")
      (libsource (lib "eagle-import") (part "USBA"))
    )
    (comp (ref "X3")
      (value "MSTBV2")
      (footprint "eagle-import:MSTBV2")
      (fields (field (name "MPN") "MSTBV 2,5/2-GF-5.08"))
      (libsource (lib "eagle-import") (part "MSTBV2"))
    )
    (comp (ref "X9")
      (value "MSTBV4")
      (footprint "eagle-import:MSTBV4")
      (fields (field (name "MPN") "MSTBV 2,5/4-GF-5.08"))
      (libsource (lib "eagle-import") (part "MSTBV4"))
    )
    (comp (ref "X10")
      (value "MSTBV4")
      (footprint "eagle-import:MSTBV4")
      (fields (field (name "MPN") "MSTBV 2,5/4-GF-5.08"))
      (libsource (lib "eagle-import") (part "MSTBV4"))
    )
    (comp (ref "X11")
      (value "MSTBV2")
      (footprint "eagle-import:MSTBV2")
      (fields (field (name "MPN") "MSTBV 2,5/2-GF-5.08"))
      (libsource (lib "eagle-import") (part "MSTBV2"))
    )
    (comp (ref "X12")
      (value "MSTBV2")
      (footprint "eagle-import:MSTBV2")
      (fields (field (name "MPN") "MSTBV 2,5/2-GF-5.08"))
      (libsource (lib "eagle-import") (part "MSTBV2"))
    )
    (comp (ref "X13")
      (value "MSTBV4")
      (footprint "eagle-import:MSTBV4")
      (fields (field (name "MPN") "MSTBV 2,5/4-GF-5.08"))
      (libsource (lib "eagle-import") (part "MSTBV4"))
    )
    (comp (ref "Y-DIR")
      (value "TPSQTP09R")
      (footprint "eagle-import:TP09R")
      (libsource (lib "eagle-import") (part "TPSQTP09R"))
    )
    (comp (ref "Y-EN")
      (value "TPSQTP09R")
      (footprint "eagle-import:TP09R")
      (libsource (lib "eagle-import") (part "TPSQTP09R"))
    )
    (comp (ref "Y-POT")
      (value "TPSQTP09R")
      (footprint "eagle-import:TP09R")
      (libsource (lib "eagle-import") (part "TPSQTP09R"))
    )
    (comp (ref "Y-STEP")
      (value "TPSQTP09R")
      (footprint "eagle-import:TP09R")
      (libsource (lib "eagle-import") (part "TPSQTP09R"))
    )
    (comp (ref "Y-STEPPER")
      (value "KK-156-4")
      (footprint "eagle-import:KK-156-4")
      (libsource (lib "eagle-import") (part "KK-156-4"))
    )
    (comp (ref "Y1")
      (value "16MHz")
      (footprint "eagle-import:HC49_S")
      (libsource (lib "eagle-import") (part "CRYTALHC49S"))
    )
    (comp (ref "Y2")
      (value "16MHz")
      (footprint "eagle-import:HC49_S")
      (libsource (lib "eagle-import") (part "CRYTALHC49S"))
    )
    (comp (ref "Z-DIR")
      (value "TPSQTP09R")
      (footprint "eagle-import:TP09R")
      (libsource (lib "eagle-import") (part "TPSQTP09R"))
    )
    (comp (ref "Z-EN")
      (value "TPSQTP09R")
      (footprint "eagle-import:TP09R")
      (libsource (lib "eagle-import") (part "TPSQTP09R"))
    )
    (comp (ref "Z-POT")
      (value "TPSQTP09R")
      (footprint "eagle-import:TP09R")
      (libsource (lib "eagle-import") (part "TPSQTP09R"))
    )
    (comp (ref "Z-STEP")
      (value "TPSQTP09R")
      (footprint "eagle-import:TP09R")
      (libsource (lib "eagle-import") (part "TPSQTP09R"))
    )
    (comp (ref "Z-STEPPER")
      (value "KK-156-4")
      (footprint "eagle-import:KK-156-4")
      (libsource (lib "eagle-import") (part "KK-156-4"))
    )
  )
  (nets
    (net (code "1") (name "+24V") (class "Default")
      (node (ref "BOTSTEP-A") (pin "8") (pinfunction "VBB_8") (pintype "bidirectional"))
      (node (ref "BOTSTEP-B") (pin "8") (pinfunction "VBB_8") (pintype "bidirectional"))
      (node (ref "BOTSTEP-X") (pin "8") (pinfunction "VBB_8") (pintype "bidirectional"))
      (node (ref "BOTSTEP-Y") (pin "8") (pinfunction "VBB_8") (pintype "bidirectional"))
      (node (ref "BOTSTEP-Z") (pin "8") (pinfunction "VBB_8") (pintype "bidirectional"))
      (node (ref "C10") (pin "1") (pinfunction "1_1") (pintype "passive"))
      (node (ref "C11") (pin "1") (pinfunction "1_1") (pintype "passive"))
      (node (ref "C12") (pin "1") (pinfunction "1_1") (pintype "passive"))
      (node (ref "C13") (pin "1") (pinfunction "1_1") (pintype "passive"))
      (node (ref "C14") (pin "1") (pinfunction "1_1") (pintype "passive"))
      (node (ref "C33") (pin "1") (pinfunction "1_1") (pintype "passive"))
      (node (ref "C34") (pin "+") (pinfunction "+_+") (pintype "passive"))
      (node (ref "C41") (pin "+") (pinfunction "+_+") (pintype "passive"))
      (node (ref "R100") (pin "2") (pinfunction "2_2") (pintype "passive"))
      (node (ref "R101") (pin "2") (pinfunction "2_2") (pintype "passive"))
      (node (ref "R102") (pin "2") (pinfunction "2_2") (pintype "passive"))
      (node (ref "R80") (pin "2") (pinfunction "2_2") (pintype "passive"))
      (node (ref "R92") (pin "2") (pinfunction "2_2") (pintype "passive"))
      (node (ref "R94") (pin "2") (pinfunction "2_2") (pintype "passive"))
      (node (ref "R98") (pin "2") (pinfunction "2_2") (pintype "passive"))
      (node (ref "RGB-LED") (pin "1") (pinfunction "S_1") (pintype "passive"))
      (node (ref "S2") (pin "P$5") (pinfunction "S_P$5") (pintype "passive"))
      (node (ref "TP35") (pin "TP") (pinfunction "TP_TP") (pintype "input"))
      (node (ref "U14") (pin "1") (pinfunction "IN_1") (pintype "input"))
      (node (ref "U6") (pin "4") (pinfunction "P2_4") (pintype "bidirectional"))
      (node (ref "U6") (pin "5") (pinfunction "N_5") (pintype "bidirectional"))
      (node (ref "U6") (pin "6") (pinfunction "P1_6") (pintype "bidirectional"))
      (node (ref "U7") (pin "4") (pinfunction "P2_4") (pintype "bidirectional"))
      (node (ref "U7") (pin "5") (pinfunction "N_5") (pintype "bidirectional"))
      (node (ref "U7") (pin "6") (pinfunction "P1_6") (pintype "bidirectional"))
      (node (ref "X1") (pin "1") (pinfunction "1_1") (pintype "passive"))
      (node (ref "X10") (pin "3") (pinfunction "1_3") (pintype "passive"))
      (node (ref "X11") (pin "1") (pinfunction "1_1") (pintype "passive"))
      (node (ref "X12") (pin "1") (pinfunction "1_1") (pintype "passive"))
      (node (ref "X9") (pin "3") (pinfunction "1_3") (pintype "passive"))
    )
    (net (code "2") (name "5V") (class "Default")
      (node (ref "BOTSTEP-A") (pin "2") (pinfunction "VCC_2") (pintype "bidirectional"))
      (node (ref "BOTSTEP-B") (pin "2") (pinfunction "VCC_2") (pintype "bidirectional"))
      (node (ref "BOTSTEP-X") (pin "2") (pinfunction "VCC_2") (pintype "bidirectional"))
      (node (ref "BOTSTEP-Y") (pin "2") (pinfunction "VCC_2") (pintype "bidirectional"))
      (node (ref "BOTSTEP-Z") (pin "2") (pinfunction "VCC_2") (pintype "bidirectional"))
      (node (ref "C16") (pin "1") (pinfunction "1_1") (pintype "passive"))
      (node (ref "C18") (pin "1") (pinfunction "1_1") (pintype "passive"))
      (node (ref "C21") (pin "1") (pinfunction "1_1") (pintype "passive"))
      (node (ref "C22") (pin "1") (pinfunction "1_1") (pintype "passive"))
      (node (ref "C23") (pin "2") (pinfunction "2_2") (pintype "passive"))
      (node (ref "C27") (pin "1") (pinfunction "1_1") (pintype "passive"))
      (node (ref "C3") (pin "2") (pinfunction "2_2") (pintype "passive"))
      (node (ref "C30") (pin "1") (pinfunction "1_1") (pintype "passive"))
      (node (ref "C31") (pin "+") (pinfunction "+_+") (pintype "passive"))
      (node (ref "C35") (pin "+") (pinfunction "+_+") (pintype "passive"))
      (node (ref "C4") (pin "2") (pinfunction "2_2") (pintype "passive"))
      (node (ref "C5") (pin "2") (pinfunction "2_2") (pintype "passive"))
      (node (ref "C6") (pin "2") (pinfunction "2_2") (pintype "passive"))
      (node (ref "C7") (pin "2") (pinfunction "2_2") (pintype "passive"))
      (node (ref "HBP-THERM") (pin "1") (pinfunction "S_1") (pintype "passive"))
      (node (ref "I2C") (pin "1") (pinfunction "1_1") (pintype "passive"))
      (node (ref "ICSP1") (pin "2") (pinfunction "2_2") (pintype "passive"))
      (node (ref "ICSP2") (pin "2") (pinfunction "2_2") (pintype "passive"))
      (node (ref "INTERFACE") (pin "1") (pinfunction "1_1") (pintype "passive"))
      (node (ref "INTERFACE") (pin "2") (pinfunction "2_2") (pintype "passive"))
      (node (ref "INTERFACE") (pin "3") (pinfunction "3_3") (pintype "passive"))
      (node (ref "JP3") (pin "3") (pinfunction "3_3") (pintype "passive"))
      (node (ref "JP3") (pin "4") (pinfunction "4_4") (pintype "passive"))
      (node (ref "JP4") (pin "3") (pinfunction "3_3") (pintype "passive"))
      (node (ref "JP4") (pin "4") (pinfunction "4_4") (pintype "passive"))
      (node (ref "JP5") (pin "3") (pinfunction "3_3") (pintype "passive"))
      (node (ref "JP5") (pin "4") (pinfunction "4_4") (pintype "passive"))
      (node (ref "JP6") (pin "3") (pinfunction "3_3") (pintype "passive"))
      (node (ref "JP6") (pin "4") (pinfunction "4_4") (pintype "passive"))
      (node (ref "JP7") (pin "3") (pinfunction "3_3") (pintype "passive"))
      (node (ref "JP7") (pin "4") (pinfunction "4_4") (pintype "passive"))
      (node (ref "L32") (pin "2") (pinfunction "2_2") (pintype "passive"))
      (node (ref "R10") (pin "2") (pinfunction "2_2") (pintype "passive"))
      (node (ref "R108") (pin "2") (pinfunction "2_2") (pintype "passive"))
      (node (ref "R109") (pin "2") (pinfunction "2_2") (pintype "passive"))
      (node (ref "R11") (pin "2") (pinfunction "2_2") (pintype "passive"))
      (node (ref "R113") (pin "1") (pinfunction "1_1") (pintype "passive"))
      (node (ref "R114") (pin "1") (pinfunction "1_1") (pintype "passive"))
      (node (ref "R115") (pin "1") (pinfunction "1_1") (pintype "passive"))
      (node (ref "R12") (pin "2") (pinfunction "2_2") (pintype "passive"))
      (node (ref "R13") (pin "2") (pinfunction "2_2") (pintype "passive"))
      (node (ref "R14") (pin "2") (pinfunction "2_2") (pintype "passive"))
      (node (ref "R15") (pin "2") (pinfunction "2_2") (pintype "passive"))
      (node (ref "R16") (pin "2") (pinfunction "2_2") (pintype "passive"))
      (node (ref "R17") (pin "2") (pinfunction "2_2") (pintype "passive"))
      (node (ref "R18") (pin "2") (pinfunction "2_2") (pintype "passive"))
      (node (ref "R19") (pin "2") (pinfunction "2_2") (pintype "passive"))
      (node (ref "R30") (pin "2") (pinfunction "2_2") (pintype "passive"))
      (node (ref "R31") (pin "2") (pinfunction "2_2") (pintype "passive"))
      (node (ref "R32") (pin "2") (pinfunction "2_2") (pintype "passive"))
      (node (ref "R34") (pin "2") (pinfunction "2_2") (pintype "passive"))
      (node (ref "R35") (pin "2") (pinfunction "2_2") (pintype "passive"))
      (node (ref "R36") (pin "2") (pinfunction "2_2") (pintype "passive"))
      (node (ref "R37") (pin "2") (pinfunction "2_2") (pintype "passive"))
      (node (ref "R38") (pin "2") (pinfunction "2_2") (pintype "passive"))
      (node (ref "R39") (pin "2") (pinfunction "2_2") (pintype "passive"))
      (node (ref "R4") (pin "2") (pinfunction "2_2") (pintype "passive"))
      (node (ref "R40") (pin "2") (pinfunction "2_2") (pintype "passive"))
      (node (ref "R41") (pin "2") (pinfunction "2_2") (pintype "passive"))
      (node (ref "R42") (pin "2") (pinfunction "2_2") (pintype "passive"))
      (node (ref "R43") (pin "2") (pinfunction "2_2") (pintype "passive"))
      (node (ref "R48") (pin "2") (pinfunction "2_2") (pintype "passive"))
      (node (ref "R5") (pin "2") (pinfunction "2_2") (pintype "passive"))
      (node (ref "R53") (pin "2") (pinfunction "2_2") (pintype "passive"))
      (node (ref "R54") (pin "2") (pinfunction "2_2") (pintype "passive"))
      (node (ref "R55") (pin "2") (pinfunction "2_2") (pintype "passive"))
      (node (ref "R6") (pin "2") (pinfunction "2_2") (pintype "passive"))
      (node (ref "R63") (pin "2") (pinfunction "2_2") (pintype "passive"))
      (node (ref "R64") (pin "2") (pinfunction "2_2") (pintype "passive"))
      (node (ref "R65") (pin "1") (pinfunction "1_1") (pintype "passive"))
      (node (ref "R7") (pin "2") (pinfunction "2_2") (pintype "passive"))
      (node (ref "R72") (pin "1") (pinfunction "1_1") (pintype "passive"))
      (node (ref "R73") (pin "1") (pinfunction "1_1") (pintype "passive"))
      (node (ref "R77") (pin "2") (pinfunction "2_2") (pintype "passive"))
      (node (ref "R78") (pin "2") (pinfunction "2_2") (pintype "passive"))
      (node (ref "R79") (pin "1") (pinfunction "1_1") (pintype "passive"))
      (node (ref "R8") (pin "2") (pinfunction "2_2") (pintype "passive"))
      (node (ref "R86") (pin "2") (pinfunction "2_2") (pintype "passive"))
      (node (ref "R9") (pin "2") (pinfunction "2_2") (pintype "passive"))
      (node (ref "R95") (pin "2") (pinfunction "2_2") (pintype "passive"))
      (node (ref "TP34") (pin "TP") (pinfunction "TP_TP") (pintype "input"))
      (node (ref "U10") (pin "1") (pinfunction "VDD_1") (pintype "bidirectional"))
      (node (ref "U11") (pin "1") (pinfunction "VDD_1") (pintype "bidirectional"))
      (node (ref "U12") (pin "1") (pinfunction "VDD_1") (pintype "bidirectional"))
      (node (ref "U14") (pin "4") (pinfunction "FB_4") (pintype "input"))
      (node (ref "U15") (pin "8") (pinfunction "VDD_8") (pintype "bidirectional"))
      (node (ref "U19") (pin "8") (pinfunction "VCC_8") (pintype "bidirectional"))
      (node (ref "U3") (pin "32") (pinfunction "AVCC_32") (pintype "power_in"))
      (node (ref "U3") (pin "4") (pinfunction "VCC_4") (pintype "power_in"))
      (node (ref "U4") (pin "10") (pinfunction "VCC_10") (pintype "power_in"))
      (node (ref "U4") (pin "100") (pinfunction "AVCC_100") (pintype "power_in"))
      (node (ref "U4") (pin "31") (pinfunction "VCC1_31") (pintype "power_in"))
      (node (ref "U4") (pin "61") (pinfunction "VCC2_61") (pintype "power_in"))
      (node (ref "U4") (pin "80") (pinfunction "VCC3_80") (pintype "power_in"))
      (node (ref "U5") (pin "8") (pinfunction "VCC_8") (pintype "bidirectional"))
      (node (ref "U8") (pin "1") (pinfunction "VDD_1") (pintype "bidirectional"))
      (node (ref "U9") (pin "1") (pinfunction "VDD_1") (pintype "bidirectional"))
      (node (ref "UART") (pin "1") (pinfunction "1_1") (pintype "passive"))
    )
    (net (code "3") (name "8U2-EX1") (class "Default")
      (node (ref "JP3") (pin "5") (pinfunction "5_5") (pintype "passive"))
      (node (ref "U3") (pin "21") (pinfunction "(PCINT7/OC0A/OC1C)PB7_21") (pintype "bidirectional"))
    )
    (net (code "4") (name "8U2-EX2") (class "Default")
      (node (ref "JP3") (pin "6") (pinfunction "6_6") (pintype "passive"))
      (node (ref "U3") (pin "20") (pinfunction "(PCINT6)PB6_20") (pintype "bidirectional"))
    )
    (net (code "5") (name "8U2-MISO") (class "Default")
      (node (ref "ICSP1") (pin "1") (pinfunction "1_1") (pintype "passive"))
      (node (ref "U3") (pin "17") (pinfunction "(PD0/MISO/PCINT3)PB3_17") (pintype "bidirectional"))
    )
    (net (code "6") (name "8U2-MOSI") (class "Default")
      (node (ref "ICSP1") (pin "4") (pinfunction "4_4") (pintype "passive"))
      (node (ref "U3") (pin "16") (pinfunction "(PDI/MOSI/PCINT2)PB2_16") (pintype "bidirectional"))
    )
    (net (code "7") (name "8U2-RESET") (class "Default")
      (node (ref "ICSP1") (pin "5") (pinfunction "5_5") (pintype "passive"))
      (node (ref "R64") (pin "1") (pinfunction "1_1") (pintype "passive"))
      (node (ref "U3") (pin "24") (pinfunction "RESET(PC1/DW)_24") (pintype "input"))
    )
    (net (code "8") (name "8U2-SCK") (class "Default")
      (node (ref "ICSP1") (pin "3") (pinfunction "3_3") (pintype "passive"))
      (node (ref "U3") (pin "15") (pinfunction "(SCLK/PCINT1)PB1_15") (pintype "bidirectional"))
    )
    (net (code "9") (name "1280-EX-RX") (class "Default")
      (node (ref "U4") (pin "45") (pinfunction "(RXD1/INT2)PD2_45") (pintype "bidirectional"))
      (node (ref "UART") (pin "4") (pinfunction "4_4") (pintype "passive"))
    )
    (net (code "10") (name "1280-EX-TX") (class "Default")
      (node (ref "U4") (pin "46") (pinfunction "(TXD1/INT3)PD3_46") (pintype "bidirectional"))
      (node (ref "UART") (pin "3") (pinfunction "3_3") (pintype "passive"))
    )
    (net (code "11") (name "1280-EX1") (class "Default")
      (node (ref "DEBUG2") (pin "A") (pinfunction "A_A") (pintype "passive"))
      (node (ref "JP4") (pin "6") (pinfunction "6_6") (pintype "passive"))
      (node (ref "U4") (pin "54") (pinfunction "(A9)PC1_54") (pintype "bidirectional"))
    )
    (net (code "12") (name "1280-EX2") (class "Default")
      (node (ref "DEBUG3") (pin "A") (pinfunction "A_A") (pintype "passive"))
      (node (ref "JP5") (pin "5") (pinfunction "5_5") (pintype "passive"))
      (node (ref "U4") (pin "53") (pinfunction "(A8)PC0_53") (pintype "bidirectional"))
    )
    (net (code "13") (name "1280-EX3") (class "Default")
      (node (ref "DEBUG4") (pin "A") (pinfunction "A_A") (pintype "passive"))
      (node (ref "JP5") (pin "6") (pinfunction "6_6") (pintype "passive"))
      (node (ref "U4") (pin "52") (pinfunction "(RD)PG1_52") (pintype "bidirectional"))
    )
    (net (code "14") (name "1280-EX4") (class "Default")
      (node (ref "JP6") (pin "5") (pinfunction "5_5") (pintype "passive"))
      (node (ref "U4") (pin "51") (pinfunction "(WR)PG0_51") (pintype "bidirectional"))
    )
    (net (code "15") (name "1280-EX5") (class "Default")
      (node (ref "JP6") (pin "6") (pinfunction "6_6") (pintype "passive"))
      (node (ref "U4") (pin "83") (pinfunction "PK6(ADC14/PCINT22)_83") (pintype "bidirectional"))
    )
    (net (code "16") (name "1280-EX6") (class "Default")
      (node (ref "JP7") (pin "5") (pinfunction "5_5") (pintype "passive"))
      (node (ref "U4") (pin "77") (pinfunction "(AD1)PA1_77") (pintype "bidirectional"))
    )
    (net (code "17") (name "1280-EX7") (class "Default")
      (node (ref "JP7") (pin "6") (pinfunction "6_6") (pintype "passive"))
      (node (ref "U4") (pin "78") (pinfunction "(AD0)PA0_78") (pintype "bidirectional"))
    )
    (net (code "18") (name "1280-MISO") (class "Default")
      (node (ref "ICSP2") (pin "1") (pinfunction "1_1") (pintype "passive"))
      (node (ref "INTERFACE") (pin "20") (pinfunction "20_20") (pintype "passive"))
      (node (ref "U4") (pin "22") (pinfunction "(MISO/PCINT3)PB3_22") (pintype "bidirectional"))
    )
    (net (code "19") (name "1280-MOSI") (class "Default")
      (node (ref "ICSP2") (pin "4") (pinfunction "4_4") (pintype "passive"))
      (node (ref "INTERFACE") (pin "19") (pinfunction "19_19") (pintype "passive"))
      (node (ref "U4") (pin "21") (pinfunction "(MOSI/PCINT2)PB2_21") (pintype "bidirectional"))
    )
    (net (code "20") (name "1280-RESET") (class "Default")
      (node (ref "C15") (pin "2") (pinfunction "2_2") (pintype "passive"))
      (node (ref "C20") (pin "1") (pinfunction "1_1") (pintype "passive"))
      (node (ref "ICSP2") (pin "5") (pinfunction "5_5") (pintype "passive"))
      (node (ref "R63") (pin "1") (pinfunction "1_1") (pintype "passive"))
      (node (ref "S1") (pin "1") (pinfunction "S_1") (pintype "passive"))
      (node (ref "U4") (pin "30") (pinfunction "RESET_30") (pintype "input"))
    )
    (net (code "21") (name "1280-RX") (class "Default")
      (node (ref "R68") (pin "2") (pinfunction "2_2") (pintype "passive"))
      (node (ref "U4") (pin "2") (pinfunction "(RXD0/PCIN8)PE0_2") (pintype "bidirectional"))
    )
    (net (code "22") (name "1280-SCK") (class "Default")
      (node (ref "ICSP2") (pin "3") (pinfunction "3_3") (pintype "passive"))
      (node (ref "INTERFACE") (pin "18") (pinfunction "18_18") (pintype "passive"))
      (node (ref "U4") (pin "20") (pinfunction "(SCK/PCINT1)PB1_20") (pintype "bidirectional"))
    )
    (net (code "23") (name "1280-TX") (class "Default")
      (node (ref "R71") (pin "2") (pinfunction "2_2") (pintype "passive"))
      (node (ref "U4") (pin "3") (pinfunction "(TXD0)PE1_3") (pintype "bidirectional"))
    )
    (net (code "24") (name "A-AXIS-DIR") (class "Default")
      (node (ref "A-DIR") (pin "TP") (pinfunction "TP_TP") (pintype "input"))
      (node (ref "BOTSTEP-A") (pin "16") (pinfunction "DIR_16") (pintype "input"))
      (node (ref "U4") (pin "76") (pinfunction "(AD2)PA2_76") (pintype "bidirectional"))
    )
    (net (code "25") (name "A-AXIS-EN") (class "Default")
      (node (ref "A-EN") (pin "TP") (pinfunction "TP_TP") (pintype "input"))
      (node (ref "BOTSTEP-A") (pin "9") (pinfunction "EN_9") (pintype "input"))
      (node (ref "R42") (pin "1") (pinfunction "1_1") (pintype "passive"))
      (node (ref "U4") (pin "74") (pinfunction "(AD4)PA4_74") (pintype "bidirectional"))
    )
    (net (code "26") (name "A-AXIS-POT") (class "Default")
      (node (ref "R106") (pin "2") (pinfunction "2_2") (pintype "passive"))
      (node (ref "U4") (pin "73") (pinfunction "(AD5)PA5_73") (pintype "bidirectional"))
    )
    (net (code "27") (name "A-AXIS-STEP") (class "Default")
      (node (ref "A-STEP") (pin "TP") (pinfunction "TP_TP") (pintype "input"))
      (node (ref "BOTSTEP-A") (pin "15") (pinfunction "STEP_15") (pintype "input"))
      (node (ref "U4") (pin "75") (pinfunction "(AD3)PA3_75") (pintype "bidirectional"))
    )
    (net (code "28") (name "AREF") (class "Default")
      (node (ref "C19") (pin "1") (pinfunction "1_1") (pintype "passive"))
      (node (ref "U4") (pin "98") (pinfunction "AREF_98") (pintype "bidirectional"))
    )
    (net (code "29") (name "B-AXIS-DIR") (class "Default")
      (node (ref "B-DIR") (pin "TP") (pinfunction "TP_TP") (pintype "input"))
      (node (ref "BOTSTEP-B") (pin "16") (pinfunction "DIR_16") (pintype "input"))
      (node (ref "U4") (pin "72") (pinfunction "(AD6)PA6_72") (pintype "bidirectional"))
    )
    (net (code "30") (name "B-AXIS-EN") (class "Default")
      (node (ref "B-EN") (pin "TP") (pinfunction "TP_TP") (pintype "input"))
      (node (ref "BOTSTEP-B") (pin "9") (pinfunction "EN_9") (pintype "input"))
      (node (ref "R43") (pin "1") (pinfunction "1_1") (pintype "passive"))
      (node (ref "U4") (pin "70") (pinfunction "(ALE)PG2_70") (pintype "bidirectional"))
    )
    (net (code "31") (name "B-AXIS-POT") (class "Default")
      (node (ref "R107") (pin "2") (pinfunction "2_2") (pintype "passive"))
      (node (ref "U4") (pin "69") (pinfunction "PJ6(PCINT15)_69") (pintype "bidirectional"))
    )
    (net (code "32") (name "B-AXIS-STEP") (class "Default")
      (node (ref "B-STEP") (pin "TP") (pinfunction "TP_TP") (pintype "input"))
      (node (ref "BOTSTEP-B") (pin "15") (pinfunction "STEP_15") (pintype "input"))
      (node (ref "U4") (pin "71") (pinfunction "(AD7)PA7_71") (pintype "bidirectional"))
    )
    (net (code "33") (name "BLINK") (class "Default")
      (node (ref "DEBUG1") (pin "A") (pinfunction "A_A") (pintype "passive"))
      (node (ref "JP4") (pin "5") (pinfunction "5_5") (pintype "passive"))
      (node (ref "U4") (pin "26") (pinfunction "(OC0A/OC1C/PCINT7)PB7_26") (pintype "bidirectional"))
    )
    (net (code "34") (name "BUZZ") (class "Default")
      (node (ref "LS1") (pin "+") (pinfunction "-_+") (pintype "passive"))
      (node (ref "U4") (pin "1") (pinfunction "(OC0B)PG5_1") (pintype "bidirectional"))
    )
    (net (code "35") (name "CUTOFF-RESET") (class "Default")
      (node (ref "R93") (pin "2") (pinfunction "2_2") (pintype "passive"))
      (node (ref "U4") (pin "13") (pinfunction "PH1(TXD2)_13") (pintype "bidirectional"))
      (node (ref "U5") (pin "1") (pinfunction "A1_1") (pintype "bidirectional"))
    )
    (net (code "36") (name "CUTOFF-SR-CHECK") (class "Default")
      (node (ref "R86") (pin "1") (pinfunction "1_1") (pintype "passive"))
      (node (ref "R91") (pin "1") (pinfunction "1_1") (pintype "passive"))
      (node (ref "U4") (pin "29") (pinfunction "(TOSC1)PG4_29") (pintype "bidirectional"))
      (node (ref "U5") (pin "6") (pinfunction "B2_6") (pintype "bidirectional"))
      (node (ref "U5") (pin "7") (pinfunction "Y1_7") (pintype "bidirectional"))
      (node (ref "U6") (pin "2") (pinfunction "K_2") (pintype "bidirectional"))
      (node (ref "U7") (pin "2") (pinfunction "K_2") (pintype "bidirectional"))
    )
    (net (code "37") (name "CUTOFF-TEST") (class "Default")
      (node (ref "R95") (pin "1") (pinfunction "1_1") (pintype "passive"))
      (node (ref "R96") (pin "1") (pinfunction "1_1") (pintype "passive"))
      (node (ref "U4") (pin "12") (pinfunction "PH0(RXD2)_12") (pintype "bidirectional"))
      (node (ref "U5") (pin "5") (pinfunction "A2_5") (pintype "bidirectional"))
    )
    (net (code "38") (name "DATA+") (class "Default")
      (node (ref "R66") (pin "2") (pinfunction "2_2") (pintype "passive"))
      (node (ref "USB+") (pin "TP") (pinfunction "TP_TP") (pintype "input"))
      (node (ref "VR2") (pin "2") (pinfunction "2_2") (pintype "passive"))
      (node (ref "X2") (pin "3") (pinfunction "3_3") (pintype "bidirectional"))
    )
    (net (code "39") (name "DATA-") (class "Default")
      (node (ref "R69") (pin "2") (pinfunction "2_2") (pintype "passive"))
      (node (ref "USB-") (pin "TP") (pinfunction "TP_TP") (pintype "input"))
      (node (ref "VR1") (pin "2") (pinfunction "2_2") (pintype "passive"))
      (node (ref "X2") (pin "2") (pinfunction "2_2") (pintype "bidirectional"))
    )
    (net (code "40") (name "EX1-FAN") (class "Default")
      (node (ref "Q2") (pin "4") (pinfunction "G_4") (pintype "passive"))
      (node (ref "R89") (pin "2") (pinfunction "2_2") (pintype "passive"))
      (node (ref "U4") (pin "16") (pinfunction "PH4(OC4B)_16") (pintype "bidirectional"))
    )
    (net (code "41") (name "EX1-HEAT") (class "Default")
      (node (ref "Q1") (pin "4") (pinfunction "G_4") (pintype "passive"))
      (node (ref "R82") (pin "2") (pinfunction "2_2") (pintype "passive"))
      (node (ref "U4") (pin "15") (pinfunction "PH3(OC4A)_15") (pintype "bidirectional"))
    )
    (net (code "42") (name "EX1-PWR") (class "Default")
      (node (ref "R97") (pin "2") (pinfunction "2_2") (pintype "passive"))
      (node (ref "X9") (pin "1") (pinfunction "1_1") (pintype "passive"))
    )
    (net (code "43") (name "EX1-PWR-CHECK") (class "Default")
      (node (ref "R87") (pin "2") (pinfunction "2_2") (pintype "passive"))
      (node (ref "R92") (pin "1") (pinfunction "1_1") (pintype "passive"))
      (node (ref "U4") (pin "14") (pinfunction "PH2(XCK2)_14") (pintype "bidirectional"))
    )
    (net (code "44") (name "EX2-FAN") (class "Default")
      (node (ref "Q4") (pin "4") (pinfunction "G_4") (pintype "passive"))
      (node (ref "R90") (pin "2") (pinfunction "2_2") (pintype "passive"))
      (node (ref "U4") (pin "25") (pinfunction "(OC1B/PCINT6)PB6_25") (pintype "bidirectional"))
    )
    (net (code "45") (name "EX2-HEAT") (class "Default")
      (node (ref "Q3") (pin "4") (pinfunction "G_4") (pintype "passive"))
      (node (ref "R83") (pin "2") (pinfunction "2_2") (pintype "passive"))
      (node (ref "U4") (pin "24") (pinfunction "(OC1A/PCINT5)PB5_24") (pintype "bidirectional"))
    )
    (net (code "46") (name "EX2-PWR") (class "Default")
      (node (ref "R99") (pin "2") (pinfunction "2_2") (pintype "passive"))
      (node (ref "X10") (pin "1") (pinfunction "1_1") (pintype "passive"))
    )
    (net (code "47") (name "EX2-PWR-CHECK") (class "Default")
      (node (ref "R88") (pin "2") (pinfunction "2_2") (pintype "passive"))
      (node (ref "R94") (pin "1") (pinfunction "1_1") (pintype "passive"))
      (node (ref "U4") (pin "23") (pinfunction "(OC2A/PCINT4)PB4_23") (pintype "bidirectional"))
    )
    (net (code "48") (name "EXTRA-FET") (class "Default")
      (node (ref "Q6") (pin "4") (pinfunction "G_4") (pintype "passive"))
      (node (ref "R85") (pin "2") (pinfunction "2_2") (pintype "passive"))
      (node (ref "U4") (pin "40") (pinfunction "PL5(OC5C)_40") (pintype "bidirectional"))
    )
    (net (code "49") (name "GND") (class "Default")
      (node (ref "24V") (pin "C") (pinfunction "C_C") (pintype "passive"))
      (node (ref "5V") (pin "C") (pinfunction "C_C") (pintype "passive"))
      (node (ref "BOTSTEP-A") (pin "1") (pinfunction "GND1_1") (pintype "bidirectional"))
      (node (ref "BOTSTEP-A") (pin "7") (pinfunction "GND2_7") (pintype "bidirectional"))
      (node (ref "BOTSTEP-B") (pin "1") (pinfunction "GND1_1") (pintype "bidirectional"))
      (node (ref "BOTSTEP-B") (pin "7") (pinfunction "GND2_7") (pintype "bidirectional"))
      (node (ref "BOTSTEP-X") (pin "1") (pinfunction "GND1_1") (pintype "bidirectional"))
      (node (ref "BOTSTEP-X") (pin "7") (pinfunction "GND2_7") (pintype "bidirectional"))
      (node (ref "BOTSTEP-Y") (pin "1") (pinfunction "GND1_1") (pintype "bidirectional"))
      (node (ref "BOTSTEP-Y") (pin "7") (pinfunction "GND2_7") (pintype "bidirectional"))
      (node (ref "BOTSTEP-Z") (pin "1") (pinfunction "GND1_1") (pintype "bidirectional"))
      (node (ref "BOTSTEP-Z") (pin "7") (pinfunction "GND2_7") (pintype "bidirectional"))
      (node (ref "C1") (pin "1") (pinfunction "1_1") (pintype "passive"))
      (node (ref "C10") (pin "2") (pinfunction "2_2") (pintype "passive"))
      (node (ref "C11") (pin "2") (pinfunction "2_2") (pintype "passive"))
      (node (ref "C12") (pin "2") (pinfunction "2_2") (pintype "passive"))
      (node (ref "C13") (pin "2") (pinfunction "2_2") (pintype "passive"))
      (node (ref "C14") (pin "2") (pinfunction "2_2") (pintype "passive"))
      (node (ref "C15") (pin "1") (pinfunction "1_1") (pintype "passive"))
      (node (ref "C16") (pin "2") (pinfunction "2_2") (pintype "passive"))
      (node (ref "C18") (pin "2") (pinfunction "2_2") (pintype "passive"))
      (node (ref "C19") (pin "2") (pinfunction "2_2") (pintype "passive"))
      (node (ref "C21") (pin "2") (pinfunction "2_2") (pintype "passive"))
      (node (ref "C22") (pin "2") (pinfunction "2_2") (pintype "passive"))
      (node (ref "C23") (pin "1") (pinfunction "1_1") (pintype "passive"))
      (node (ref "C24") (pin "1") (pinfunction "1_1") (pintype "passive"))
      (node (ref "C25") (pin "1") (pinfunction "1_1") (pintype "passive"))
      (node (ref "C26") (pin "1") (pinfunction "1_1") (pintype "passive"))
      (node (ref "C27") (pin "2") (pinfunction "2_2") (pintype "passive"))
      (node (ref "C28") (pin "1") (pinfunction "1_1") (pintype "passive"))
      (node (ref "C29") (pin "1") (pinfunction "1_1") (pintype "passive"))
      (node (ref "C3") (pin "1") (pinfunction "1_1") (pintype "passive"))
      (node (ref "C30") (pin "2") (pinfunction "2_2") (pintype "passive"))
      (node (ref "C31") (pin "-") (pinfunction "-_-") (pintype "passive"))
      (node (ref "C32") (pin "1") (pinfunction "1_1") (pintype "passive"))
      (node (ref "C33") (pin "2") (pinfunction "2_2") (pintype "passive"))
      (node (ref "C34") (pin "-") (pinfunction "-_-") (pintype "passive"))
      (node (ref "C35") (pin "-") (pinfunction "-_-") (pintype "passive"))
      (node (ref "C36") (pin "1") (pinfunction "1_1") (pintype "passive"))
      (node (ref "C37") (pin "1") (pinfunction "1_1") (pintype "passive"))
      (node (ref "C38") (pin "1") (pinfunction "1_1") (pintype "passive"))
      (node (ref "C39") (pin "1") (pinfunction "1_1") (pintype "passive"))
      (node (ref "C4") (pin "1") (pinfunction "1_1") (pintype "passive"))
      (node (ref "C40") (pin "1") (pinfunction "1_1") (pintype "passive"))
      (node (ref "C41") (pin "-") (pinfunction "-_-") (pintype "passive"))
      (node (ref "C5") (pin "1") (pinfunction "1_1") (pintype "passive"))
      (node (ref "C6") (pin "1") (pinfunction "1_1") (pintype "passive"))
      (node (ref "C7") (pin "1") (pinfunction "1_1") (pintype "passive"))
      (node (ref "C9") (pin "1") (pinfunction "1_1") (pintype "passive"))
      (node (ref "D1") (pin "A") (pinfunction "A_A") (pintype "passive"))
      (node (ref "HBP-THERM") (pin "2") (pinfunction "S_2") (pintype "passive"))
      (node (ref "HBP-THERM") (pin "3") (pinfunction "S_3") (pintype "passive"))
      (node (ref "I2C") (pin "2") (pinfunction "2_2") (pintype "passive"))
      (node (ref "ICSP1") (pin "6") (pinfunction "6_6") (pintype "passive"))
      (node (ref "ICSP2") (pin "6") (pinfunction "6_6") (pintype "passive"))
      (node (ref "INTERFACE") (pin "21") (pinfunction "21_21") (pintype "passive"))
      (node (ref "INTERFACE") (pin "22") (pinfunction "22_22") (pintype "passive"))
      (node (ref "INTERFACE") (pin "23") (pinfunction "23_23") (pintype "passive"))
      (node (ref "INTERFACE") (pin "24") (pinfunction "24_24") (pintype "passive"))
      (node (ref "INTERFACE") (pin "25") (pinfunction "25_25") (pintype "passive"))
      (node (ref "INTERFACE") (pin "26") (pinfunction "26_26") (pintype "passive"))
      (node (ref "J2") (pin "GND") (pinfunction "GND_GND") (pintype "bidirectional"))
      (node (ref "J2") (pin "GNDBREAK") (pinfunction "GNDBREAK_GNDBREAK") (pintype "bidirectional"))
      (node (ref "JP1") (pin "2") (pinfunction "2_2") (pintype "passive"))
      (node (ref "JP10") (pin "2") (pinfunction "2_2") (pintype "passive"))
      (node (ref "JP11") (pin "2") (pinfunction "2_2") (pintype "passive"))
      (node (ref "JP12") (pin "2") (pinfunction "2_2") (pintype "passive"))
      (node (ref "JP13") (pin "2") (pinfunction "2_2") (pintype "passive"))
      (node (ref "JP2") (pin "1") (pinfunction "1_1") (pintype "passive"))
      (node (ref "JP3") (pin "1") (pinfunction "1_1") (pintype "passive"))
      (node (ref "JP3") (pin "2") (pinfunction "2_2") (pintype "passive"))
      (node (ref "JP4") (pin "1") (pinfunction "1_1") (pintype "passive"))
      (node (ref "JP4") (pin "2") (pinfunction "2_2") (pintype "passive"))
      (node (ref "JP5") (pin "1") (pinfunction "1_1") (pintype "passive"))
      (node (ref "JP5") (pin "2") (pinfunction "2_2") (pintype "passive"))
      (node (ref "JP6") (pin "1") (pinfunction "1_1") (pintype "passive"))
      (node (ref "JP6") (pin "2") (pinfunction "2_2") (pintype "passive"))
      (node (ref "JP7") (pin "1") (pinfunction "1_1") (pintype "passive"))
      (node (ref "JP7") (pin "2") (pinfunction "2_2") (pintype "passive"))
      (node (ref "JP8") (pin "1") (pinfunction "1_1") (pintype "passive"))
      (node (ref "JP9") (pin "2") (pinfunction "2_2") (pintype "passive"))
      (node (ref "LS1") (pin "-") (pinfunction "+_-") (pintype "passive"))
      (node (ref "OVERHEAT") (pin "C") (pinfunction "C_C") (pintype "passive"))
      (node (ref "Q1") (pin "1") (pinfunction "S_1") (pintype "passive"))
      (node (ref "Q1") (pin "2") (pinfunction "S_2") (pintype "passive"))
      (node (ref "Q1") (pin "3") (pinfunction "S_3") (pintype "passive"))
      (node (ref "Q2") (pin "1") (pinfunction "S_1") (pintype "passive"))
      (node (ref "Q2") (pin "2") (pinfunction "S_2") (pintype "passive"))
      (node (ref "Q2") (pin "3") (pinfunction "S_3") (pintype "passive"))
      (node (ref "Q3") (pin "1") (pinfunction "S_1") (pintype "passive"))
      (node (ref "Q3") (pin "2") (pinfunction "S_2") (pintype "passive"))
      (node (ref "Q3") (pin "3") (pinfunction "S_3") (pintype "passive"))
      (node (ref "Q4") (pin "1") (pinfunction "S_1") (pintype "passive"))
      (node (ref "Q4") (pin "2") (pinfunction "S_2") (pintype "passive"))
      (node (ref "Q4") (pin "3") (pinfunction "S_3") (pintype "passive"))
      (node (ref "Q5") (pin "1") (pinfunction "S_1") (pintype "passive"))
      (node (ref "Q5") (pin "2") (pinfunction "S_2") (pintype "passive"))
      (node (ref "Q5") (pin "3") (pinfunction "S_3") (pintype "passive"))
      (node (ref "Q6") (pin "1") (pinfunction "S_1") (pintype "passive"))
      (node (ref "Q6") (pin "2") (pinfunction "S_2") (pintype "passive"))
      (node (ref "Q6") (pin "3") (pinfunction "S_3") (pintype "passive"))
      (node (ref "R1") (pin "1") (pinfunction "1_1") (pintype "passive"))
      (node (ref "R20") (pin "1") (pinfunction "1_1") (pintype "passive"))
      (node (ref "R21") (pin "1") (pinfunction "1_1") (pintype "passive"))
      (node (ref "R22") (pin "1") (pinfunction "1_1") (pintype "passive"))
      (node (ref "R23") (pin "1") (pinfunction "1_1") (pintype "passive"))
      (node (ref "R24") (pin "1") (pinfunction "1_1") (pintype "passive"))
      (node (ref "R25") (pin "1") (pinfunction "1_1") (pintype "passive"))
      (node (ref "R26") (pin "1") (pinfunction "1_1") (pintype "passive"))
      (node (ref "R27") (pin "1") (pinfunction "1_1") (pintype "passive"))
      (node (ref "R28") (pin "1") (pinfunction "1_1") (pintype "passive"))
      (node (ref "R29") (pin "1") (pinfunction "1_1") (pintype "passive"))
      (node (ref "R67") (pin "2") (pinfunction "2_2") (pintype "passive"))
      (node (ref "R70") (pin "1") (pinfunction "1_1") (pintype "passive"))
      (node (ref "R74") (pin "1") (pinfunction "1_1") (pintype "passive"))
      (node (ref "R75") (pin "1") (pinfunction "1_1") (pintype "passive"))
      (node (ref "R76") (pin "1") (pinfunction "1_1") (pintype "passive"))
      (node (ref "R82") (pin "1") (pinfunction "1_1") (pintype "passive"))
      (node (ref "R83") (pin "1") (pinfunction "1_1") (pintype "passive"))
      (node (ref "R84") (pin "1") (pinfunction "1_1") (pintype "passive"))
      (node (ref "R85") (pin "1") (pinfunction "1_1") (pintype "passive"))
      (node (ref "R87") (pin "1") (pinfunction "1_1") (pintype "passive"))
      (node (ref "R88") (pin "1") (pinfunction "1_1") (pintype "passive"))
      (node (ref "R89") (pin "1") (pinfunction "1_1") (pintype "passive"))
      (node (ref "R90") (pin "1") (pinfunction "1_1") (pintype "passive"))
      (node (ref "R93") (pin "1") (pinfunction "1_1") (pintype "passive"))
      (node (ref "S1") (pin "3") (pinfunction "P_3") (pintype "passive"))
      (node (ref "U10") (pin "2") (pinfunction "VSS_2") (pintype "bidirectional"))
      (node (ref "U11") (pin "2") (pinfunction "VSS_2") (pintype "bidirectional"))
      (node (ref "U12") (pin "2") (pinfunction "VSS_2") (pintype "bidirectional"))
      (node (ref "U14") (pin "3") (pinfunction "GND_3") (pintype "power_in"))
      (node (ref "U14") (pin "5") (pinfunction "EN_5") (pintype "input"))
      (node (ref "U14") (pin "6") (pinfunction "GND_6") (pintype "power_in"))
      (node (ref "U15") (pin "4") (pinfunction "VSS_4") (pintype "bidirectional"))
      (node (ref "U16") (pin "2") (pinfunction "S_2") (pintype "bidirectional"))
      (node (ref "U17") (pin "2") (pinfunction "S_2") (pintype "bidirectional"))
      (node (ref "U18") (pin "2") (pinfunction "S_2") (pintype "bidirectional"))
      (node (ref "U19") (pin "4") (pinfunction "GND_4") (pintype "bidirectional"))
      (node (ref "U3") (pin "3") (pinfunction "GND_3") (pintype "power_in"))
      (node (ref "U3") (pin "EXP") (pinfunction "PAD_EXP") (pintype "power_in"))
      (node (ref "U4") (pin "11") (pinfunction "GND_11") (pintype "power_in"))
      (node (ref "U4") (pin "32") (pinfunction "GND1_32") (pintype "power_in"))
      (node (ref "U4") (pin "62") (pinfunction "GND2_62") (pintype "power_in"))
      (node (ref "U4") (pin "81") (pinfunction "GND3_81") (pintype "power_in"))
      (node (ref "U4") (pin "99") (pinfunction "AGND_99") (pintype "power_in"))
      (node (ref "U5") (pin "4") (pinfunction "GND_4") (pintype "bidirectional"))
      (node (ref "U8") (pin "2") (pinfunction "VSS_2") (pintype "bidirectional"))
      (node (ref "U9") (pin "2") (pinfunction "VSS_2") (pintype "bidirectional"))
      (node (ref "UART") (pin "2") (pinfunction "2_2") (pintype "passive"))
      (node (ref "X1") (pin "2") (pinfunction "1_2") (pintype "passive"))
      (node (ref "X13") (pin "2") (pinfunction "1_2") (pintype "passive"))
      (node (ref "X13") (pin "4") (pinfunction "1_4") (pintype "passive"))
      (node (ref "X3") (pin "2") (pinfunction "1_2") (pintype "passive"))
    )
    (net (code "50") (name "HBP") (class "Default")
      (node (ref "Q5") (pin "4") (pinfunction "G_4") (pintype "passive"))
      (node (ref "R84") (pin "2") (pinfunction "2_2") (pintype "passive"))
      (node (ref "U4") (pin "39") (pinfunction "PL4(OC5B)_39") (pintype "bidirectional"))
    )
    (net (code "51") (name "HBP-THERM") (class "Default")
      (node (ref "HBP-THERM") (pin "4") (pinfunction "S_4") (pintype "passive"))
      (node (ref "R65") (pin "2") (pinfunction "2_2") (pintype "passive"))
      (node (ref "TP27") (pin "TP") (pinfunction "TP_TP") (pintype "input"))
      (node (ref "U4") (pin "82") (pinfunction "PK7(ADC15/PCINT23)_82") (pintype "bidirectional"))
    )
    (net (code "52") (name "I4-UP") (class "Default")
      (node (ref "INTERFACE") (pin "4") (pinfunction "4_4") (pintype "passive"))
      (node (ref "U4") (pin "67") (pinfunction "PJ4(PCINT13)_67") (pintype "bidirectional"))
    )
    (net (code "53") (name "I5-DOWN") (class "Default")
      (node (ref "INTERFACE") (pin "5") (pinfunction "5_5") (pintype "passive"))
      (node (ref "U4") (pin "66") (pinfunction "PJ3(PCINT12)_66") (pintype "bidirectional"))
    )
    (net (code "54") (name "I6-LEFT") (class "Default")
      (node (ref "INTERFACE") (pin "6") (pinfunction "6_6") (pintype "passive"))
      (node (ref "U4") (pin "65") (pinfunction "PJ2(XCK3/PCINT11)_65") (pintype "bidirectional"))
    )
    (net (code "55") (name "I7-RIGHT") (class "Default")
      (node (ref "INTERFACE") (pin "7") (pinfunction "7_7") (pintype "passive"))
      (node (ref "U4") (pin "64") (pinfunction "PJ1(TXD3/PCINT10)_64") (pintype "bidirectional"))
    )
    (net (code "56") (name "I8-CENTER") (class "Default")
      (node (ref "INTERFACE") (pin "8") (pinfunction "8_8") (pintype "passive"))
      (node (ref "U4") (pin "63") (pinfunction "PJ0(RXD3/PCINT9)_63") (pintype "bidirectional"))
    )
    (net (code "57") (name "I9-DETECT") (class "Default")
      (node (ref "INTERFACE") (pin "9") (pinfunction "9_9") (pintype "passive"))
      (node (ref "R70") (pin "2") (pinfunction "2_2") (pintype "passive"))
      (node (ref "U4") (pin "60") (pinfunction "(A15)PC7_60") (pintype "bidirectional"))
    )
    (net (code "58") (name "I10-GLED") (class "Default")
      (node (ref "INTERFACE") (pin "10") (pinfunction "10_10") (pintype "passive"))
      (node (ref "U4") (pin "59") (pinfunction "(A14)PC6_59") (pintype "bidirectional"))
    )
    (net (code "59") (name "I11-RLED") (class "Default")
      (node (ref "INTERFACE") (pin "11") (pinfunction "11_11") (pintype "passive"))
      (node (ref "U4") (pin "58") (pinfunction "(A13)PC5_58") (pintype "bidirectional"))
    )
    (net (code "60") (name "I12-LCD-STROBE") (class "Default")
      (node (ref "INTERFACE") (pin "12") (pinfunction "12_12") (pintype "passive"))
      (node (ref "U4") (pin "57") (pinfunction "(A12)PC4_57") (pintype "bidirectional"))
    )
    (net (code "61") (name "I13-LCD-DATA") (class "Default")
      (node (ref "INTERFACE") (pin "13") (pinfunction "13_13") (pintype "passive"))
      (node (ref "U4") (pin "56") (pinfunction "(A11)PC3_56") (pintype "bidirectional"))
    )
    (net (code "62") (name "I14-LCD-CLK") (class "Default")
      (node (ref "INTERFACE") (pin "14") (pinfunction "14_14") (pintype "passive"))
      (node (ref "U4") (pin "55") (pinfunction "(A10)PC2_55") (pintype "bidirectional"))
    )
    (net (code "63") (name "Net-(5V-PadA)") (class "Default")
      (node (ref "5V") (pin "A") (pinfunction "A_A") (pintype "passive"))
      (node (ref "R79") (pin "2") (pinfunction "2_2") (pintype "passive"))
    )
    (net (code "64") (name "Net-(24V-PadA)") (class "Default")
      (node (ref "24V") (pin "A") (pinfunction "A_A") (pintype "passive"))
      (node (ref "R80") (pin "1") (pinfunction "1_1") (pintype "passive"))
    )
    (net (code "65") (name "Net-(A-STEPPERA-S)") (class "Default")
      (node (ref "A-STEPPER") (pin "1") (pinfunction "S_1") (pintype "passive"))
      (node (ref "BOTSTEP-A") (pin "4") (pinfunction "OUT1A_4") (pintype "output"))
    )
    (net (code "66") (name "Net-(A-STEPPERB-S)") (class "Default")
      (node (ref "A-STEPPER") (pin "2") (pinfunction "S_2") (pintype "passive"))
      (node (ref "BOTSTEP-A") (pin "3") (pinfunction "OUT1B_3") (pintype "output"))
    )
    (net (code "67") (name "Net-(A-STEPPERC-S)") (class "Default")
      (node (ref "A-STEPPER") (pin "3") (pinfunction "S_3") (pintype "passive"))
      (node (ref "BOTSTEP-A") (pin "5") (pinfunction "OUT2A_5") (pintype "output"))
    )
    (net (code "68") (name "Net-(A-STEPPERD-S)") (class "Default")
      (node (ref "A-STEPPER") (pin "4") (pinfunction "S_4") (pintype "passive"))
      (node (ref "BOTSTEP-A") (pin "6") (pinfunction "OUT2B_6") (pintype "output"))
    )
    (net (code "69") (name "Net-(B-STEPPERA-S)") (class "Default")
      (node (ref "B-STEPPER") (pin "1") (pinfunction "S_1") (pintype "passive"))
      (node (ref "BOTSTEP-B") (pin "4") (pinfunction "OUT1A_4") (pintype "output"))
    )
    (net (code "70") (name "Net-(B-STEPPERB-S)") (class "Default")
      (node (ref "B-STEPPER") (pin "2") (pinfunction "S_2") (pintype "passive"))
      (node (ref "BOTSTEP-B") (pin "3") (pinfunction "OUT1B_3") (pintype "output"))
    )
    (net (code "71") (name "Net-(B-STEPPERC-S)") (class "Default")
      (node (ref "B-STEPPER") (pin "3") (pinfunction "S_3") (pintype "passive"))
      (node (ref "BOTSTEP-B") (pin "5") (pinfunction "OUT2A_5") (pintype "output"))
    )
    (net (code "72") (name "Net-(B-STEPPERD-S)") (class "Default")
      (node (ref "B-STEPPER") (pin "4") (pinfunction "S_4") (pintype "passive"))
      (node (ref "BOTSTEP-B") (pin "6") (pinfunction "OUT2B_6") (pintype "output"))
    )
    (net (code "73") (name "Net-(BOTSTEP-A-MS1)") (class "Default")
      (node (ref "BOTSTEP-A") (pin "10") (pinfunction "MS1_10") (pintype "input"))
      (node (ref "R14") (pin "1") (pinfunction "1_1") (pintype "passive"))
      (node (ref "R26") (pin "2") (pinfunction "2_2") (pintype "passive"))
    )
    (net (code "74") (name "Net-(BOTSTEP-A-MS2)") (class "Default")
      (node (ref "BOTSTEP-A") (pin "11") (pinfunction "MS2_11") (pintype "input"))
      (node (ref "R15") (pin "1") (pinfunction "1_1") (pintype "passive"))
      (node (ref "R27") (pin "2") (pinfunction "2_2") (pintype "passive"))
    )
    (net (code "75") (name "Net-(BOTSTEP-A-RST)") (class "Default")
      (node (ref "BOTSTEP-A") (pin "13") (pinfunction "RST_13") (pintype "input"))
      (node (ref "BOTSTEP-A") (pin "14") (pinfunction "SLP_14") (pintype "input"))
      (node (ref "R16") (pin "1") (pinfunction "1_1") (pintype "passive"))
    )
    (net (code "76") (name "Net-(BOTSTEP-A-VREF)") (class "Default")
      (node (ref "BOTSTEP-A") (pin "12") (pinfunction "VREF_12") (pintype "input"))
      (node (ref "U11") (pin "5") (pinfunction "W_5") (pintype "bidirectional"))
    )
    (net (code "77") (name "Net-(BOTSTEP-B-MS1)") (class "Default")
      (node (ref "BOTSTEP-B") (pin "10") (pinfunction "MS1_10") (pintype "input"))
      (node (ref "R17") (pin "1") (pinfunction "1_1") (pintype "passive"))
      (node (ref "R28") (pin "2") (pinfunction "2_2") (pintype "passive"))
    )
    (net (code "78") (name "Net-(BOTSTEP-B-MS2)") (class "Default")
      (node (ref "BOTSTEP-B") (pin "11") (pinfunction "MS2_11") (pintype "input"))
      (node (ref "R18") (pin "1") (pinfunction "1_1") (pintype "passive"))
      (node (ref "R29") (pin "2") (pinfunction "2_2") (pintype "passive"))
    )
    (net (code "79") (name "Net-(BOTSTEP-B-RST)") (class "Default")
      (node (ref "BOTSTEP-B") (pin "13") (pinfunction "RST_13") (pintype "input"))
      (node (ref "BOTSTEP-B") (pin "14") (pinfunction "SLP_14") (pintype "input"))
      (node (ref "R19") (pin "1") (pinfunction "1_1") (pintype "passive"))
    )
    (net (code "80") (name "Net-(BOTSTEP-B-VREF)") (class "Default")
      (node (ref "BOTSTEP-B") (pin "12") (pinfunction "VREF_12") (pintype "input"))
      (node (ref "U12") (pin "5") (pinfunction "W_5") (pintype "bidirectional"))
    )
    (net (code "81") (name "Net-(BOTSTEP-X-MS1)") (class "Default")
      (node (ref "BOTSTEP-X") (pin "10") (pinfunction "MS1_10") (pintype "input"))
      (node (ref "R20") (pin "2") (pinfunction "2_2") (pintype "passive"))
      (node (ref "R5") (pin "1") (pinfunction "1_1") (pintype "passive"))
    )
    (net (code "82") (name "Net-(BOTSTEP-X-MS2)") (class "Default")
      (node (ref "BOTSTEP-X") (pin "11") (pinfunction "MS2_11") (pintype "input"))
      (node (ref "R21") (pin "2") (pinfunction "2_2") (pintype "passive"))
      (node (ref "R6") (pin "1") (pinfunction "1_1") (pintype "passive"))
    )
    (net (code "83") (name "Net-(BOTSTEP-X-OUT1A)") (class "Default")
      (node (ref "BOTSTEP-X") (pin "4") (pinfunction "OUT1A_4") (pintype "output"))
      (node (ref "X-STEPPER") (pin "1") (pinfunction "S_1") (pintype "passive"))
    )
    (net (code "84") (name "Net-(BOTSTEP-X-OUT1B)") (class "Default")
      (node (ref "BOTSTEP-X") (pin "3") (pinfunction "OUT1B_3") (pintype "output"))
      (node (ref "X-STEPPER") (pin "2") (pinfunction "S_2") (pintype "passive"))
    )
    (net (code "85") (name "Net-(BOTSTEP-X-OUT2A)") (class "Default")
      (node (ref "BOTSTEP-X") (pin "5") (pinfunction "OUT2A_5") (pintype "output"))
      (node (ref "X-STEPPER") (pin "3") (pinfunction "S_3") (pintype "passive"))
    )
    (net (code "86") (name "Net-(BOTSTEP-X-OUT2B)") (class "Default")
      (node (ref "BOTSTEP-X") (pin "6") (pinfunction "OUT2B_6") (pintype "output"))
      (node (ref "X-STEPPER") (pin "4") (pinfunction "S_4") (pintype "passive"))
    )
    (net (code "87") (name "Net-(BOTSTEP-X-RST)") (class "Default")
      (node (ref "BOTSTEP-X") (pin "13") (pinfunction "RST_13") (pintype "input"))
      (node (ref "BOTSTEP-X") (pin "14") (pinfunction "SLP_14") (pintype "input"))
      (node (ref "R7") (pin "1") (pinfunction "1_1") (pintype "passive"))
    )
    (net (code "88") (name "Net-(BOTSTEP-X-VREF)") (class "Default")
      (node (ref "BOTSTEP-X") (pin "12") (pinfunction "VREF_12") (pintype "input"))
      (node (ref "U8") (pin "5") (pinfunction "W_5") (pintype "bidirectional"))
    )
    (net (code "89") (name "Net-(BOTSTEP-Y-MS1)") (class "Default")
      (node (ref "BOTSTEP-Y") (pin "10") (pinfunction "MS1_10") (pintype "input"))
      (node (ref "R22") (pin "2") (pinfunction "2_2") (pintype "passive"))
      (node (ref "R8") (pin "1") (pinfunction "1_1") (pintype "passive"))
    )
    (net (code "90") (name "Net-(BOTSTEP-Y-MS2)") (class "Default")
      (node (ref "BOTSTEP-Y") (pin "11") (pinfunction "MS2_11") (pintype "input"))
      (node (ref "R23") (pin "2") (pinfunction "2_2") (pintype "passive"))
      (node (ref "R9") (pin "1") (pinfunction "1_1") (pintype "passive"))
    )
    (net (code "91") (name "Net-(BOTSTEP-Y-OUT1A)") (class "Default")
      (node (ref "BOTSTEP-Y") (pin "4") (pinfunction "OUT1A_4") (pintype "output"))
      (node (ref "Y-STEPPER") (pin "1") (pinfunction "S_1") (pintype "passive"))
    )
    (net (code "92") (name "Net-(BOTSTEP-Y-OUT1B)") (class "Default")
      (node (ref "BOTSTEP-Y") (pin "3") (pinfunction "OUT1B_3") (pintype "output"))
      (node (ref "Y-STEPPER") (pin "2") (pinfunction "S_2") (pintype "passive"))
    )
    (net (code "93") (name "Net-(BOTSTEP-Y-OUT2A)") (class "Default")
      (node (ref "BOTSTEP-Y") (pin "5") (pinfunction "OUT2A_5") (pintype "output"))
      (node (ref "Y-STEPPER") (pin "3") (pinfunction "S_3") (pintype "passive"))
    )
    (net (code "94") (name "Net-(BOTSTEP-Y-OUT2B)") (class "Default")
      (node (ref "BOTSTEP-Y") (pin "6") (pinfunction "OUT2B_6") (pintype "output"))
      (node (ref "Y-STEPPER") (pin "4") (pinfunction "S_4") (pintype "passive"))
    )
    (net (code "95") (name "Net-(BOTSTEP-Y-RST)") (class "Default")
      (node (ref "BOTSTEP-Y") (pin "13") (pinfunction "RST_13") (pintype "input"))
      (node (ref "BOTSTEP-Y") (pin "14") (pinfunction "SLP_14") (pintype "input"))
      (node (ref "R10") (pin "1") (pinfunction "1_1") (pintype "passive"))
    )
    (net (code "96") (name "Net-(BOTSTEP-Y-VREF)") (class "Default")
      (node (ref "BOTSTEP-Y") (pin "12") (pinfunction "VREF_12") (pintype "input"))
      (node (ref "U9") (pin "5") (pinfunction "W_5") (pintype "bidirectional"))
    )
    (net (code "97") (name "Net-(BOTSTEP-Z-MS1)") (class "Default")
      (node (ref "BOTSTEP-Z") (pin "10") (pinfunction "MS1_10") (pintype "input"))
      (node (ref "R11") (pin "1") (pinfunction "1_1") (pintype "passive"))
      (node (ref "R24") (pin "2") (pinfunction "2_2") (pintype "passive"))
    )
    (net (code "98") (name "Net-(BOTSTEP-Z-MS2)") (class "Default")
      (node (ref "BOTSTEP-Z") (pin "11") (pinfunction "MS2_11") (pintype "input"))
      (node (ref "R12") (pin "1") (pinfunction "1_1") (pintype "passive"))
      (node (ref "R25") (pin "2") (pinfunction "2_2") (pintype "passive"))
    )
    (net (code "99") (name "Net-(BOTSTEP-Z-OUT1A)") (class "Default")
      (node (ref "BOTSTEP-Z") (pin "4") (pinfunction "OUT1A_4") (pintype "output"))
      (node (ref "Z-STEPPER") (pin "1") (pinfunction "S_1") (pintype "passive"))
    )
    (net (code "100") (name "Net-(BOTSTEP-Z-OUT1B)") (class "Default")
      (node (ref "BOTSTEP-Z") (pin "3") (pinfunction "OUT1B_3") (pintype "output"))
      (node (ref "Z-STEPPER") (pin "2") (pinfunction "S_2") (pintype "passive"))
    )
    (net (code "101") (name "Net-(BOTSTEP-Z-OUT2A)") (class "Default")
      (node (ref "BOTSTEP-Z") (pin "5") (pinfunction "OUT2A_5") (pintype "output"))
      (node (ref "Z-STEPPER") (pin "3") (pinfunction "S_3") (pintype "passive"))
    )
    (net (code "102") (name "Net-(BOTSTEP-Z-OUT2B)") (class "Default")
      (node (ref "BOTSTEP-Z") (pin "6") (pinfunction "OUT2B_6") (pintype "output"))
      (node (ref "Z-STEPPER") (pin "4") (pinfunction "S_4") (pintype "passive"))
    )
    (net (code "103") (name "Net-(BOTSTEP-Z-RST)") (class "Default")
      (node (ref "BOTSTEP-Z") (pin "13") (pinfunction "RST_13") (pintype "input"))
      (node (ref "BOTSTEP-Z") (pin "14") (pinfunction "SLP_14") (pintype "input"))
      (node (ref "R13") (pin "1") (pinfunction "1_1") (pintype "passive"))
    )
    (net (code "104") (name "Net-(BOTSTEP-Z-VREF)") (class "Default")
      (node (ref "BOTSTEP-Z") (pin "12") (pinfunction "VREF_12") (pintype "input"))
      (node (ref "U10") (pin "5") (pinfunction "W_5") (pintype "bidirectional"))
    )
    (net (code "105") (name "Net-(DEBUG1-PadC)") (class "Default")
      (node (ref "DEBUG1") (pin "C") (pinfunction "C_C") (pintype "passive"))
      (node (ref "R1") (pin "2") (pinfunction "2_2") (pintype "passive"))
    )
    (net (code "106") (name "Net-(DEBUG2-PadC)") (class "Default")
      (node (ref "DEBUG2") (pin "C") (pinfunction "C_C") (pintype "passive"))
      (node (ref "R74") (pin "2") (pinfunction "2_2") (pintype "passive"))
    )
    (net (code "107") (name "Net-(DEBUG3-PadC)") (class "Default")
      (node (ref "DEBUG3") (pin "C") (pinfunction "C_C") (pintype "passive"))
      (node (ref "R75") (pin "2") (pinfunction "2_2") (pintype "passive"))
    )
    (net (code "108") (name "Net-(DEBUG4-PadC)") (class "Default")
      (node (ref "DEBUG4") (pin "C") (pinfunction "C_C") (pintype "passive"))
      (node (ref "R76") (pin "2") (pinfunction "2_2") (pintype "passive"))
    )
    (net (code "109") (name "Net-(FET1-PadA)") (class "Default")
      (node (ref "FET1") (pin "A") (pinfunction "A_A") (pintype "passive"))
      (node (ref "R97") (pin "1") (pinfunction "1_1") (pintype "passive"))
    )
    (net (code "110") (name "Net-(FET2-PadA)") (class "Default")
      (node (ref "FET2") (pin "A") (pinfunction "A_A") (pintype "passive"))
      (node (ref "R98") (pin "1") (pinfunction "1_1") (pintype "passive"))
    )
    (net (code "111") (name "Net-(FET3-PadA)") (class "Default")
      (node (ref "FET3") (pin "A") (pinfunction "A_A") (pintype "passive"))
      (node (ref "R99") (pin "1") (pinfunction "1_1") (pintype "passive"))
    )
    (net (code "112") (name "Net-(FET4-PadA)") (class "Default")
      (node (ref "FET4") (pin "A") (pinfunction "A_A") (pintype "passive"))
      (node (ref "R100") (pin "1") (pinfunction "1_1") (pintype "passive"))
    )
    (net (code "113") (name "Net-(FET5-PadA)") (class "Default")
      (node (ref "FET5") (pin "A") (pinfunction "A_A") (pintype "passive"))
      (node (ref "R101") (pin "1") (pinfunction "1_1") (pintype "passive"))
    )
    (net (code "114") (name "Net-(FET6-PadA)") (class "Default")
      (node (ref "FET6") (pin "A") (pinfunction "A_A") (pintype "passive"))
      (node (ref "R102") (pin "1") (pinfunction "1_1") (pintype "passive"))
    )
    (net (code "115") (name "Net-(L1-Pad2)") (class "Default")
      (node (ref "L1") (pin "2") (pinfunction "2_2") (pintype "passive"))
      (node (ref "VR1") (pin "1") (pinfunction "1_1") (pintype "passive"))
      (node (ref "VR2") (pin "1") (pinfunction "1_1") (pintype "passive"))
      (node (ref "X2") (pin "P$1") (pinfunction "P$1_P$1") (pintype "bidirectional"))
      (node (ref "X2") (pin "P$2") (pinfunction "P$2_P$2") (pintype "bidirectional"))
    )
    (net (code "116") (name "Net-(OVERHEAT-PadA)") (class "Default")
      (node (ref "OVERHEAT") (pin "A") (pinfunction "A_A") (pintype "passive"))
      (node (ref "R91") (pin "2") (pinfunction "2_2") (pintype "passive"))
    )
    (net (code "117") (name "Net-(Q1-D)") (class "Default")
      (node (ref "FET1") (pin "C") (pinfunction "C_C") (pintype "passive"))
      (node (ref "Q1") (pin "MB") (pinfunction "D_MB") (pintype "passive"))
      (node (ref "X9") (pin "2") (pinfunction "1_2") (pintype "passive"))
    )
    (net (code "118") (name "Net-(Q2-D)") (class "Default")
      (node (ref "FET2") (pin "C") (pinfunction "C_C") (pintype "passive"))
      (node (ref "Q2") (pin "MB") (pinfunction "D_MB") (pintype "passive"))
      (node (ref "X9") (pin "4") (pinfunction "1_4") (pintype "passive"))
    )
    (net (code "119") (name "Net-(Q3-D)") (class "Default")
      (node (ref "FET3") (pin "C") (pinfunction "C_C") (pintype "passive"))
      (node (ref "Q3") (pin "MB") (pinfunction "D_MB") (pintype "passive"))
      (node (ref "X10") (pin "2") (pinfunction "1_2") (pintype "passive"))
    )
    (net (code "120") (name "Net-(Q4-D)") (class "Default")
      (node (ref "FET4") (pin "C") (pinfunction "C_C") (pintype "passive"))
      (node (ref "Q4") (pin "MB") (pinfunction "D_MB") (pintype "passive"))
      (node (ref "X10") (pin "4") (pinfunction "1_4") (pintype "passive"))
    )
    (net (code "121") (name "Net-(Q5-D)") (class "Default")
      (node (ref "FET5") (pin "C") (pinfunction "C_C") (pintype "passive"))
      (node (ref "Q5") (pin "MB") (pinfunction "D_MB") (pintype "passive"))
      (node (ref "X11") (pin "2") (pinfunction "1_2") (pintype "passive"))
    )
    (net (code "122") (name "Net-(Q6-D)") (class "Default")
      (node (ref "FET6") (pin "C") (pinfunction "C_C") (pintype "passive"))
      (node (ref "Q6") (pin "MB") (pinfunction "D_MB") (pintype "passive"))
      (node (ref "X12") (pin "2") (pinfunction "1_2") (pintype "passive"))
    )
    (net (code "123") (name "Net-(R72-Pad2)") (class "Default")
      (node (ref "R72") (pin "2") (pinfunction "2_2") (pintype "passive"))
      (node (ref "TX") (pin "A") (pinfunction "A_A") (pintype "passive"))
    )
    (net (code "124") (name "Net-(R73-Pad2)") (class "Default")
      (node (ref "R73") (pin "2") (pinfunction "2_2") (pintype "passive"))
      (node (ref "RX") (pin "A") (pinfunction "A_A") (pintype "passive"))
    )
    (net (code "125") (name "Net-(R96-Pad2)") (class "Default")
      (node (ref "R96") (pin "2") (pinfunction "2_2") (pintype "passive"))
      (node (ref "X3") (pin "1") (pinfunction "1_1") (pintype "passive"))
    )
    (net (code "126") (name "Net-(RGB-LEDB-S)") (class "Default")
      (node (ref "RGB-LED") (pin "2") (pinfunction "S_2") (pintype "passive"))
      (node (ref "U16") (pin "3") (pinfunction "D_3") (pintype "bidirectional"))
    )
    (net (code "127") (name "Net-(RGB-LEDC-S)") (class "Default")
      (node (ref "RGB-LED") (pin "3") (pinfunction "S_3") (pintype "passive"))
      (node (ref "U17") (pin "3") (pinfunction "D_3") (pintype "bidirectional"))
    )
    (net (code "128") (name "Net-(RGB-LEDD-S)") (class "Default")
      (node (ref "RGB-LED") (pin "4") (pinfunction "S_4") (pintype "passive"))
      (node (ref "U18") (pin "3") (pinfunction "D_3") (pintype "bidirectional"))
    )
    (net (code "129") (name "Net-(S2-P)") (class "Default")
      (node (ref "J2") (pin "PWR") (pinfunction "PWR_PWR") (pintype "bidirectional"))
      (node (ref "S2") (pin "P$4") (pinfunction "P_P$4") (pintype "passive"))
    )
    (net (code "130") (name "Net-(U3-(CTS{slash}HWB{slash}AIN6{slash}TO{slash}INT7)PD7)") (class "Default")
      (node (ref "C20") (pin "2") (pinfunction "2_2") (pintype "passive"))
      (node (ref "U3") (pin "13") (pinfunction "(CTS/HWB/AIN6/TO/INT7)PD7_13") (pintype "bidirectional"))
    )
    (net (code "131") (name "Net-(U3-(RXD1{slash}AIN1{slash}INT2)PD2)") (class "Default")
      (node (ref "R71") (pin "1") (pinfunction "1_1") (pintype "passive"))
      (node (ref "U3") (pin "8") (pinfunction "(RXD1/AIN1/INT2)PD2_8") (pintype "bidirectional"))
    )
    (net (code "132") (name "Net-(U3-(TXD1{slash}INT3)PD3)") (class "Default")
      (node (ref "R68") (pin "1") (pinfunction "1_1") (pintype "passive"))
      (node (ref "U3") (pin "9") (pinfunction "(TXD1/INT3)PD3_9") (pintype "bidirectional"))
    )
    (net (code "133") (name "Net-(U3-D+)") (class "Default")
      (node (ref "R66") (pin "1") (pinfunction "1_1") (pintype "passive"))
      (node (ref "U3") (pin "29") (pinfunction "D+_29") (pintype "bidirectional"))
    )
    (net (code "134") (name "Net-(U3-D-)") (class "Default")
      (node (ref "R69") (pin "1") (pinfunction "1_1") (pintype "passive"))
      (node (ref "U3") (pin "30") (pinfunction "D-_30") (pintype "bidirectional"))
    )
    (net (code "135") (name "Net-(U3-UCAP)") (class "Default")
      (node (ref "C17") (pin "2") (pinfunction "2_2") (pintype "passive"))
      (node (ref "U3") (pin "27") (pinfunction "UCAP_27") (pintype "passive"))
    )
    (net (code "136") (name "Net-(U3-XTAL1)") (class "Default")
      (node (ref "C25") (pin "2") (pinfunction "2_2") (pintype "passive"))
      (node (ref "U3") (pin "1") (pinfunction "XTAL1_1") (pintype "bidirectional"))
      (node (ref "Y1") (pin "1") (pinfunction "1_1") (pintype "passive"))
    )
    (net (code "137") (name "Net-(U3-XTAL2(PC0))") (class "Default")
      (node (ref "C26") (pin "2") (pinfunction "2_2") (pintype "passive"))
      (node (ref "U3") (pin "2") (pinfunction "XTAL2(PC0)_2") (pintype "bidirectional"))
      (node (ref "Y1") (pin "2") (pinfunction "2_2") (pintype "passive"))
    )
    (net (code "138") (name "Net-(U4-XTAL1)") (class "Default")
      (node (ref "C28") (pin "2") (pinfunction "2_2") (pintype "passive"))
      (node (ref "U4") (pin "34") (pinfunction "XTAL1_34") (pintype "input"))
      (node (ref "Y2") (pin "1") (pinfunction "1_1") (pintype "passive"))
    )
    (net (code "139") (name "Net-(U4-XTAL2)") (class "Default")
      (node (ref "C29") (pin "2") (pinfunction "2_2") (pintype "passive"))
      (node (ref "U4") (pin "33") (pinfunction "XTAL2_33") (pintype "output"))
      (node (ref "Y2") (pin "2") (pinfunction "2_2") (pintype "passive"))
    )
    (net (code "140") (name "Net-(U5-B1)") (class "Default")
      (node (ref "U5") (pin "2") (pinfunction "B1_2") (pintype "bidirectional"))
      (node (ref "U5") (pin "3") (pinfunction "Y2_3") (pintype "bidirectional"))
    )
    (net (code "141") (name "Net-(U6-A)") (class "Default")
      (node (ref "R108") (pin "1") (pinfunction "1_1") (pintype "passive"))
      (node (ref "U6") (pin "1") (pinfunction "A_1") (pintype "bidirectional"))
    )
    (net (code "142") (name "Net-(U7-A)") (class "Default")
      (node (ref "R109") (pin "1") (pinfunction "1_1") (pintype "passive"))
      (node (ref "U7") (pin "1") (pinfunction "A_1") (pintype "bidirectional"))
    )
    (net (code "143") (name "Net-(U8-A)") (class "Default")
      (node (ref "R34") (pin "1") (pinfunction "1_1") (pintype "passive"))
      (node (ref "U8") (pin "6") (pinfunction "A_6") (pintype "bidirectional"))
    )
    (net (code "144") (name "Net-(U8-SDA)") (class "Default")
      (node (ref "R103") (pin "1") (pinfunction "1_1") (pintype "passive"))
      (node (ref "U8") (pin "4") (pinfunction "SDA_4") (pintype "bidirectional"))
      (node (ref "X-POT") (pin "TP") (pinfunction "TP_TP") (pintype "input"))
    )
    (net (code "145") (name "Net-(U9-A)") (class "Default")
      (node (ref "R35") (pin "1") (pinfunction "1_1") (pintype "passive"))
      (node (ref "U9") (pin "6") (pinfunction "A_6") (pintype "bidirectional"))
    )
    (net (code "146") (name "Net-(U9-SDA)") (class "Default")
      (node (ref "R104") (pin "1") (pinfunction "1_1") (pintype "passive"))
      (node (ref "U9") (pin "4") (pinfunction "SDA_4") (pintype "bidirectional"))
      (node (ref "Y-POT") (pin "TP") (pinfunction "TP_TP") (pintype "input"))
    )
    (net (code "147") (name "Net-(U10-A)") (class "Default")
      (node (ref "R36") (pin "1") (pinfunction "1_1") (pintype "passive"))
      (node (ref "U10") (pin "6") (pinfunction "A_6") (pintype "bidirectional"))
    )
    (net (code "148") (name "Net-(U10-SDA)") (class "Default")
      (node (ref "R105") (pin "1") (pinfunction "1_1") (pintype "passive"))
      (node (ref "U10") (pin "4") (pinfunction "SDA_4") (pintype "bidirectional"))
      (node (ref "Z-POT") (pin "TP") (pinfunction "TP_TP") (pintype "input"))
    )
    (net (code "149") (name "Net-(U11-A)") (class "Default")
      (node (ref "R37") (pin "1") (pinfunction "1_1") (pintype "passive"))
      (node (ref "U11") (pin "6") (pinfunction "A_6") (pintype "bidirectional"))
    )
    (net (code "150") (name "Net-(U11-SDA)") (class "Default")
      (node (ref "A-POT") (pin "TP") (pinfunction "TP_TP") (pintype "input"))
      (node (ref "R106") (pin "1") (pinfunction "1_1") (pintype "passive"))
      (node (ref "U11") (pin "4") (pinfunction "SDA_4") (pintype "bidirectional"))
    )
    (net (code "151") (name "Net-(U12-A)") (class "Default")
      (node (ref "R38") (pin "1") (pinfunction "1_1") (pintype "passive"))
      (node (ref "U12") (pin "6") (pinfunction "A_6") (pintype "bidirectional"))
    )
    (net (code "152") (name "Net-(U12-SDA)") (class "Default")
      (node (ref "B-POT") (pin "TP") (pinfunction "TP_TP") (pintype "input"))
      (node (ref "R107") (pin "1") (pinfunction "1_1") (pintype "passive"))
      (node (ref "U12") (pin "4") (pinfunction "SDA_4") (pintype "bidirectional"))
    )
    (net (code "153") (name "Net-(U14-OUT)") (class "Default")
      (node (ref "D1") (pin "C") (pinfunction "C_C") (pintype "passive"))
      (node (ref "L32") (pin "1") (pinfunction "1_1") (pintype "passive"))
      (node (ref "U14") (pin "2") (pinfunction "OUT_2") (pintype "output"))
    )
    (net (code "154") (name "Net-(U15-LED0)") (class "Default")
      (node (ref "R110") (pin "2") (pinfunction "2_2") (pintype "passive"))
      (node (ref "U15") (pin "1") (pinfunction "LED0_1") (pintype "bidirectional"))
    )
    (net (code "155") (name "Net-(U15-LED1)") (class "Default")
      (node (ref "R111") (pin "2") (pinfunction "2_2") (pintype "passive"))
      (node (ref "U15") (pin "2") (pinfunction "LED1_2") (pintype "bidirectional"))
    )
    (net (code "156") (name "Net-(U15-LED2)") (class "Default")
      (node (ref "R112") (pin "2") (pinfunction "2_2") (pintype "passive"))
      (node (ref "U15") (pin "3") (pinfunction "LED2_3") (pintype "bidirectional"))
    )
    (net (code "157") (name "Net-(U16-G)") (class "Default")
      (node (ref "U16") (pin "1") (pinfunction "G_1") (pintype "bidirectional"))
      (node (ref "U19") (pin "7") (pinfunction "1Y_7") (pintype "bidirectional"))
    )
    (net (code "158") (name "Net-(U17-G)") (class "Default")
      (node (ref "U17") (pin "1") (pinfunction "G_1") (pintype "bidirectional"))
      (node (ref "U19") (pin "5") (pinfunction "2Y_5") (pintype "bidirectional"))
    )
    (net (code "159") (name "Net-(U18-G)") (class "Default")
      (node (ref "U18") (pin "1") (pinfunction "G_1") (pintype "bidirectional"))
      (node (ref "U19") (pin "2") (pinfunction "3Y_2") (pintype "bidirectional"))
    )
    (net (code "160") (name "Net-(U19-1A)") (class "Default")
      (node (ref "R110") (pin "1") (pinfunction "1_1") (pintype "passive"))
      (node (ref "R113") (pin "2") (pinfunction "2_2") (pintype "passive"))
      (node (ref "U19") (pin "1") (pinfunction "1A_1") (pintype "bidirectional"))
    )
    (net (code "161") (name "Net-(U19-2A)") (class "Default")
      (node (ref "R111") (pin "1") (pinfunction "1_1") (pintype "passive"))
      (node (ref "R114") (pin "2") (pinfunction "2_2") (pintype "passive"))
      (node (ref "U19") (pin "3") (pinfunction "2A_3") (pintype "bidirectional"))
    )
    (net (code "162") (name "Net-(U19-3A)") (class "Default")
      (node (ref "R112") (pin "1") (pinfunction "1_1") (pintype "passive"))
      (node (ref "R115") (pin "2") (pinfunction "2_2") (pintype "passive"))
      (node (ref "U19") (pin "6") (pinfunction "3A_6") (pintype "bidirectional"))
    )
    (net (code "163") (name "POTS-SCL") (class "Default")
      (node (ref "POTS-SCL") (pin "TP") (pinfunction "TP_TP") (pintype "input"))
      (node (ref "U10") (pin "3") (pinfunction "SCL_3") (pintype "bidirectional"))
      (node (ref "U11") (pin "3") (pinfunction "SCL_3") (pintype "bidirectional"))
      (node (ref "U12") (pin "3") (pinfunction "SCL_3") (pintype "bidirectional"))
      (node (ref "U4") (pin "68") (pinfunction "PJ5(PCINT14)_68") (pintype "bidirectional"))
      (node (ref "U8") (pin "3") (pinfunction "SCL_3") (pintype "bidirectional"))
      (node (ref "U9") (pin "3") (pinfunction "SCL_3") (pintype "bidirectional"))
    )
    (net (code "164") (name "RX-LED") (class "Default")
      (node (ref "RX") (pin "C") (pinfunction "C_C") (pintype "passive"))
      (node (ref "U3") (pin "10") (pinfunction "(INT5/AIN3)PD4_10") (pintype "bidirectional"))
    )
    (net (code "165") (name "SCL") (class "Default")
      (node (ref "I2C") (pin "4") (pinfunction "4_4") (pintype "passive"))
      (node (ref "R78") (pin "1") (pinfunction "1_1") (pintype "passive"))
      (node (ref "U15") (pin "6") (pinfunction "SCL_6") (pintype "bidirectional"))
      (node (ref "U4") (pin "43") (pinfunction "(SCL/INT0)PD0_43") (pintype "bidirectional"))
    )
    (net (code "166") (name "SD-CD") (class "Default")
      (node (ref "INTERFACE") (pin "16") (pinfunction "16_16") (pintype "passive"))
      (node (ref "U4") (pin "18") (pinfunction "PH6(OC2B)_18") (pintype "bidirectional"))
    )
    (net (code "167") (name "SD-CS") (class "Default")
      (node (ref "INTERFACE") (pin "17") (pinfunction "17_17") (pintype "passive"))
      (node (ref "U4") (pin "19") (pinfunction "(SS/PCINT0)PB0_19") (pintype "bidirectional"))
    )
    (net (code "168") (name "SD-WP") (class "Default")
      (node (ref "INTERFACE") (pin "15") (pinfunction "15_15") (pintype "passive"))
      (node (ref "U4") (pin "17") (pinfunction "PH5(OC4C)_17") (pintype "bidirectional"))
    )
    (net (code "169") (name "SDA") (class "Default")
      (node (ref "I2C") (pin "3") (pinfunction "3_3") (pintype "passive"))
      (node (ref "R77") (pin "1") (pinfunction "1_1") (pintype "passive"))
      (node (ref "U15") (pin "7") (pinfunction "SDA_7") (pintype "bidirectional"))
      (node (ref "U4") (pin "44") (pinfunction "(SDA/INT1)PD1_44") (pintype "bidirectional"))
    )
    (net (code "170") (name "TEMP1") (class "Default")
      (node (ref "C9") (pin "2") (pinfunction "2_2") (pintype "passive"))
      (node (ref "R53") (pin "1") (pinfunction "1_1") (pintype "passive"))
      (node (ref "U4") (pin "84") (pinfunction "PK5(ADC13/PCINT21)_84") (pintype "bidirectional"))
      (node (ref "X13") (pin "1") (pinfunction "1_1") (pintype "passive"))
    )
    (net (code "171") (name "TEMP2") (class "Default")
      (node (ref "C1") (pin "2") (pinfunction "2_2") (pintype "passive"))
      (node (ref "R48") (pin "1") (pinfunction "1_1") (pintype "passive"))
      (node (ref "U4") (pin "85") (pinfunction "PK4(ADC12/PCINT20)_85") (pintype "bidirectional"))
      (node (ref "X13") (pin "3") (pinfunction "1_3") (pintype "passive"))
    )
    (net (code "172") (name "TX-LED") (class "Default")
      (node (ref "TX") (pin "C") (pinfunction "C_C") (pintype "passive"))
      (node (ref "U3") (pin "11") (pinfunction "(XCK/AIN4/PCINT12)PD5_11") (pintype "bidirectional"))
    )
    (net (code "173") (name "UGND") (class "Default")
      (node (ref "C17") (pin "1") (pinfunction "1_1") (pintype "passive"))
      (node (ref "L1") (pin "1") (pinfunction "1_1") (pintype "passive"))
      (node (ref "R67") (pin "1") (pinfunction "1_1") (pintype "passive"))
      (node (ref "U3") (pin "28") (pinfunction "UGND_28") (pintype "power_in"))
      (node (ref "UGND") (pin "TP") (pinfunction "TP_TP") (pintype "input"))
      (node (ref "X2") (pin "4") (pinfunction "4_4") (pintype "bidirectional"))
    )
    (net (code "174") (name "UVCC") (class "Default")
      (node (ref "C24") (pin "2") (pinfunction "2_2") (pintype "passive"))
      (node (ref "U3") (pin "31") (pinfunction "UVCC_31") (pintype "power_in"))
      (node (ref "UVCC") (pin "TP") (pinfunction "TP_TP") (pintype "input"))
      (node (ref "X2") (pin "1") (pinfunction "1_1") (pintype "bidirectional"))
    )
    (net (code "175") (name "X-AXIS-DIR") (class "Default")
      (node (ref "BOTSTEP-X") (pin "16") (pinfunction "DIR_16") (pintype "input"))
      (node (ref "U4") (pin "97") (pinfunction "(ADC0)PF0_97") (pintype "bidirectional"))
      (node (ref "X-DIR") (pin "TP") (pinfunction "TP_TP") (pintype "input"))
    )
    (net (code "176") (name "X-AXIS-EN") (class "Default")
      (node (ref "BOTSTEP-X") (pin "9") (pinfunction "EN_9") (pintype "input"))
      (node (ref "R39") (pin "1") (pinfunction "1_1") (pintype "passive"))
      (node (ref "U4") (pin "95") (pinfunction "(ADC2)PF2_95") (pintype "bidirectional"))
      (node (ref "X-EN") (pin "TP") (pinfunction "TP_TP") (pintype "input"))
    )
    (net (code "177") (name "X-AXIS-POT") (class "Default")
      (node (ref "R103") (pin "2") (pinfunction "2_2") (pintype "passive"))
      (node (ref "U4") (pin "94") (pinfunction "(ADC3)PF3_94") (pintype "bidirectional"))
    )
    (net (code "178") (name "X-AXIS-STEP") (class "Default")
      (node (ref "BOTSTEP-X") (pin "15") (pinfunction "STEP_15") (pintype "input"))
      (node (ref "U4") (pin "96") (pinfunction "(ADC1)PF1_96") (pintype "bidirectional"))
      (node (ref "X-STEP") (pin "TP") (pinfunction "TP_TP") (pintype "input"))
    )
    (net (code "179") (name "X-MAX") (class "Default")
      (node (ref "C38") (pin "2") (pinfunction "2_2") (pintype "passive"))
      (node (ref "JP11") (pin "1") (pinfunction "1_1") (pintype "passive"))
      (node (ref "R32") (pin "1") (pinfunction "1_1") (pintype "passive"))
      (node (ref "TP29") (pin "TP") (pinfunction "TP_TP") (pintype "input"))
      (node (ref "U4") (pin "36") (pinfunction "PL1(ICP5)_36") (pintype "bidirectional"))
    )
    (net (code "180") (name "X-MIN") (class "Default")
      (node (ref "C32") (pin "2") (pinfunction "2_2") (pintype "passive"))
      (node (ref "JP1") (pin "1") (pinfunction "1_1") (pintype "passive"))
      (node (ref "R4") (pin "1") (pinfunction "1_1") (pintype "passive"))
      (node (ref "TP28") (pin "TP") (pinfunction "TP_TP") (pintype "input"))
      (node (ref "U4") (pin "35") (pinfunction "PL0(ICP4)_35") (pintype "bidirectional"))
    )
    (net (code "181") (name "Y-AXIS-DIR") (class "Default")
      (node (ref "BOTSTEP-Y") (pin "16") (pinfunction "DIR_16") (pintype "input"))
      (node (ref "U4") (pin "93") (pinfunction "(ADC4/TCK)PF4_93") (pintype "bidirectional"))
      (node (ref "Y-DIR") (pin "TP") (pinfunction "TP_TP") (pintype "input"))
    )
    (net (code "182") (name "Y-AXIS-EN") (class "Default")
      (node (ref "BOTSTEP-Y") (pin "9") (pinfunction "EN_9") (pintype "input"))
      (node (ref "R40") (pin "1") (pinfunction "1_1") (pintype "passive"))
      (node (ref "U4") (pin "91") (pinfunction "(ADC6/TDO)PF6_91") (pintype "bidirectional"))
      (node (ref "Y-EN") (pin "TP") (pinfunction "TP_TP") (pintype "input"))
    )
    (net (code "183") (name "Y-AXIS-POT") (class "Default")
      (node (ref "R104") (pin "2") (pinfunction "2_2") (pintype "passive"))
      (node (ref "U4") (pin "90") (pinfunction "(ADC7/TDI)PF7_90") (pintype "bidirectional"))
    )
    (net (code "184") (name "Y-AXIS-STEP") (class "Default")
      (node (ref "BOTSTEP-Y") (pin "15") (pinfunction "STEP_15") (pintype "input"))
      (node (ref "U4") (pin "92") (pinfunction "(ADC5/TMS)PF5_92") (pintype "bidirectional"))
      (node (ref "Y-STEP") (pin "TP") (pinfunction "TP_TP") (pintype "input"))
    )
    (net (code "185") (name "Y-MAX") (class "Default")
      (node (ref "C39") (pin "2") (pinfunction "2_2") (pintype "passive"))
      (node (ref "JP12") (pin "1") (pinfunction "1_1") (pintype "passive"))
      (node (ref "R54") (pin "1") (pinfunction "1_1") (pintype "passive"))
      (node (ref "TP31") (pin "TP") (pinfunction "TP_TP") (pintype "input"))
      (node (ref "U4") (pin "38") (pinfunction "PL3(OC5A)_38") (pintype "bidirectional"))
    )
    (net (code "186") (name "Y-MIN") (class "Default")
      (node (ref "C36") (pin "2") (pinfunction "2_2") (pintype "passive"))
      (node (ref "JP9") (pin "1") (pinfunction "1_1") (pintype "passive"))
      (node (ref "R30") (pin "1") (pinfunction "1_1") (pintype "passive"))
      (node (ref "TP30") (pin "TP") (pinfunction "TP_TP") (pintype "input"))
      (node (ref "U4") (pin "37") (pinfunction "PL2(T5)_37") (pintype "bidirectional"))
    )
    (net (code "187") (name "Z-AXIS-DIR") (class "Default")
      (node (ref "BOTSTEP-Z") (pin "16") (pinfunction "DIR_16") (pintype "input"))
      (node (ref "U4") (pin "89") (pinfunction "PK0(ADC8/PCINT16)_89") (pintype "bidirectional"))
      (node (ref "Z-DIR") (pin "TP") (pinfunction "TP_TP") (pintype "input"))
    )
    (net (code "188") (name "Z-AXIS-EN") (class "Default")
      (node (ref "BOTSTEP-Z") (pin "9") (pinfunction "EN_9") (pintype "input"))
      (node (ref "R41") (pin "1") (pinfunction "1_1") (pintype "passive"))
      (node (ref "U4") (pin "87") (pinfunction "PK2(ADC10/PCINT18)_87") (pintype "bidirectional"))
      (node (ref "Z-EN") (pin "TP") (pinfunction "TP_TP") (pintype "input"))
    )
    (net (code "189") (name "Z-AXIS-POT") (class "Default")
      (node (ref "R105") (pin "2") (pinfunction "2_2") (pintype "passive"))
      (node (ref "U4") (pin "86") (pinfunction "PK3(ADC11/PCINT19)_86") (pintype "bidirectional"))
    )
    (net (code "190") (name "Z-AXIS-STEP") (class "Default")
      (node (ref "BOTSTEP-Z") (pin "15") (pinfunction "STEP_15") (pintype "input"))
      (node (ref "U4") (pin "88") (pinfunction "PK1(ADC9/PCINT17)_88") (pintype "bidirectional"))
      (node (ref "Z-STEP") (pin "TP") (pinfunction "TP_TP") (pintype "input"))
    )
    (net (code "191") (name "Z-MAX") (class "Default")
      (node (ref "C40") (pin "2") (pinfunction "2_2") (pintype "passive"))
      (node (ref "JP13") (pin "1") (pinfunction "1_1") (pintype "passive"))
      (node (ref "R55") (pin "1") (pinfunction "1_1") (pintype "passive"))
      (node (ref "TP33") (pin "TP") (pinfunction "TP_TP") (pintype "input"))
      (node (ref "U4") (pin "42") (pinfunction "PL7_42") (pintype "bidirectional"))
    )
    (net (code "192") (name "Z-MIN") (class "Default")
      (node (ref "C37") (pin "2") (pinfunction "2_2") (pintype "passive"))
      (node (ref "JP10") (pin "1") (pinfunction "1_1") (pintype "passive"))
      (node (ref "R31") (pin "1") (pinfunction "1_1") (pintype "passive"))
      (node (ref "TP32") (pin "TP") (pinfunction "TP_TP") (pintype "input"))
      (node (ref "U4") (pin "41") (pinfunction "PL6_41") (pintype "bidirectional"))
    )
    (net (code "193") (name "unconnected-(S1-P1-Pad4)") (class "Default")
      (node (ref "S1") (pin "4") (pinfunction "P1_4") (pintype "passive"))
    )
    (net (code "194") (name "unconnected-(S1-S1-Pad2)") (class "Default")
      (node (ref "S1") (pin "2") (pinfunction "S1_2") (pintype "passive"))
    )
    (net (code "195") (name "unconnected-(S2-O-PadP$3)") (class "Default")
      (node (ref "S2") (pin "P$3") (pinfunction "O_P$3") (pintype "passive"))
    )
    (net (code "196") (name "unconnected-(U3-(AIN0{slash}INT1)PD1-Pad7)") (class "Default")
      (node (ref "U3") (pin "7") (pinfunction "(AIN0/INT1)PD1_7") (pintype "bidirectional"))
    )
    (net (code "197") (name "unconnected-(U3-(AIN2{slash}PCINT11)PC2-Pad5)") (class "Default")
      (node (ref "U3") (pin "5") (pinfunction "(AIN2/PCINT11)PC2_5") (pintype "bidirectional"))
    )
    (net (code "198") (name "unconnected-(U3-(INT4{slash}ICP1{slash}CLK0)PC7-Pad22)") (class "Default")
      (node (ref "U3") (pin "22") (pinfunction "(INT4/ICP1/CLK0)PC7_22") (pintype "bidirectional"))
    )
    (net (code "199") (name "unconnected-(U3-(OC0B{slash}INT0)PD0-Pad6)") (class "Default")
      (node (ref "U3") (pin "6") (pinfunction "(OC0B/INT0)PD0_6") (pintype "bidirectional"))
    )
    (net (code "200") (name "unconnected-(U3-(OC1A{slash}PCINT8)PC6-Pad23)") (class "Default")
      (node (ref "U3") (pin "23") (pinfunction "(OC1A/PCINT8)PC6_23") (pintype "bidirectional"))
    )
    (net (code "201") (name "unconnected-(U3-(PCINT5)PB5-Pad19)") (class "Default")
      (node (ref "U3") (pin "19") (pinfunction "(PCINT5)PB5_19") (pintype "bidirectional"))
    )
    (net (code "202") (name "unconnected-(U3-(PCINT9{slash}OC1B)PC5-Pad25)") (class "Default")
      (node (ref "U3") (pin "25") (pinfunction "(PCINT9/OC1B)PC5_25") (pintype "bidirectional"))
    )
    (net (code "203") (name "unconnected-(U3-(PCINT10)PC4-Pad26)") (class "Default")
      (node (ref "U3") (pin "26") (pinfunction "(PCINT10)PC4_26") (pintype "bidirectional"))
    )
    (net (code "204") (name "unconnected-(U3-(RTS{slash}AIN5{slash}INT6)PD6-Pad12)") (class "Default")
      (node (ref "U3") (pin "12") (pinfunction "(RTS/AIN5/INT6)PD6_12") (pintype "bidirectional"))
    )
    (net (code "205") (name "unconnected-(U3-(SS{slash}PCINT0)PB0-Pad14)") (class "Default")
      (node (ref "U3") (pin "14") (pinfunction "(SS/PCINT0)PB0_14") (pintype "bidirectional"))
    )
    (net (code "206") (name "unconnected-(U3-(T1{slash}PCINT4)PB4-Pad18)") (class "Default")
      (node (ref "U3") (pin "18") (pinfunction "(T1/PCINT4)PB4_18") (pintype "bidirectional"))
    )
    (net (code "207") (name "unconnected-(U4-(CLKO{slash}ICP3{slash}INT7)PE7-Pad9)") (class "Default")
      (node (ref "U4") (pin "9") (pinfunction "(CLKO/ICP3/INT7)PE7_9") (pintype "bidirectional"))
    )
    (net (code "208") (name "unconnected-(U4-(ICP1)PD4-Pad47)") (class "Default")
      (node (ref "U4") (pin "47") (pinfunction "(ICP1)PD4_47") (pintype "bidirectional"))
    )
    (net (code "209") (name "unconnected-(U4-(OC3A{slash}AIN1)PE3-Pad5)") (class "Default")
      (node (ref "U4") (pin "5") (pinfunction "(OC3A/AIN1)PE3_5") (pintype "bidirectional"))
    )
    (net (code "210") (name "unconnected-(U4-(OC3B{slash}INT4)PE4-Pad6)") (class "Default")
      (node (ref "U4") (pin "6") (pinfunction "(OC3B/INT4)PE4_6") (pintype "bidirectional"))
    )
    (net (code "211") (name "unconnected-(U4-(OC3C{slash}INT5)PE5-Pad7)") (class "Default")
      (node (ref "U4") (pin "7") (pinfunction "(OC3C/INT5)PE5_7") (pintype "bidirectional"))
    )
    (net (code "212") (name "unconnected-(U4-(T0)PD7-Pad50)") (class "Default")
      (node (ref "U4") (pin "50") (pinfunction "(T0)PD7_50") (pintype "bidirectional"))
    )
    (net (code "213") (name "unconnected-(U4-(T1)PD6-Pad49)") (class "Default")
      (node (ref "U4") (pin "49") (pinfunction "(T1)PD6_49") (pintype "bidirectional"))
    )
    (net (code "214") (name "unconnected-(U4-(T3{slash}INT6)PE6-Pad8)") (class "Default")
      (node (ref "U4") (pin "8") (pinfunction "(T3/INT6)PE6_8") (pintype "bidirectional"))
    )
    (net (code "215") (name "unconnected-(U4-(TOSC2)PG3-Pad28)") (class "Default")
      (node (ref "U4") (pin "28") (pinfunction "(TOSC2)PG3_28") (pintype "bidirectional"))
    )
    (net (code "216") (name "unconnected-(U4-(XCK0{slash}AIN0)PE2-Pad4)") (class "Default")
      (node (ref "U4") (pin "4") (pinfunction "(XCK0/AIN0)PE2_4") (pintype "bidirectional"))
    )
    (net (code "217") (name "unconnected-(U4-(XCK1)PD5-Pad48)") (class "Default")
      (node (ref "U4") (pin "48") (pinfunction "(XCK1)PD5_48") (pintype "bidirectional"))
    )
    (net (code "218") (name "unconnected-(U4-PH7(T4)-Pad27)") (class "Default")
      (node (ref "U4") (pin "27") (pinfunction "PH7(T4)_27") (pintype "bidirectional"))
    )
    (net (code "219") (name "unconnected-(U4-PJ7-Pad79)") (class "Default")
      (node (ref "U4") (pin "79") (pinfunction "PJ7_79") (pintype "bidirectional"))
    )
    (net (code "220") (name "unconnected-(U6-NC-Pad3)") (class "Default")
      (node (ref "U6") (pin "3") (pinfunction "NC_3") (pintype "bidirectional"))
    )
    (net (code "221") (name "unconnected-(U7-NC-Pad3)") (class "Default")
      (node (ref "U7") (pin "3") (pinfunction "NC_3") (pintype "bidirectional"))
    )
    (net (code "222") (name "unconnected-(U15-LED3-Pad5)") (class "Default")
      (node (ref "U15") (pin "5") (pinfunction "LED3_5") (pintype "bidirectional"))
    )
  )
)
